# Work_In_Progress.net
KiCad netlist of a schematic drawn in EAGLE
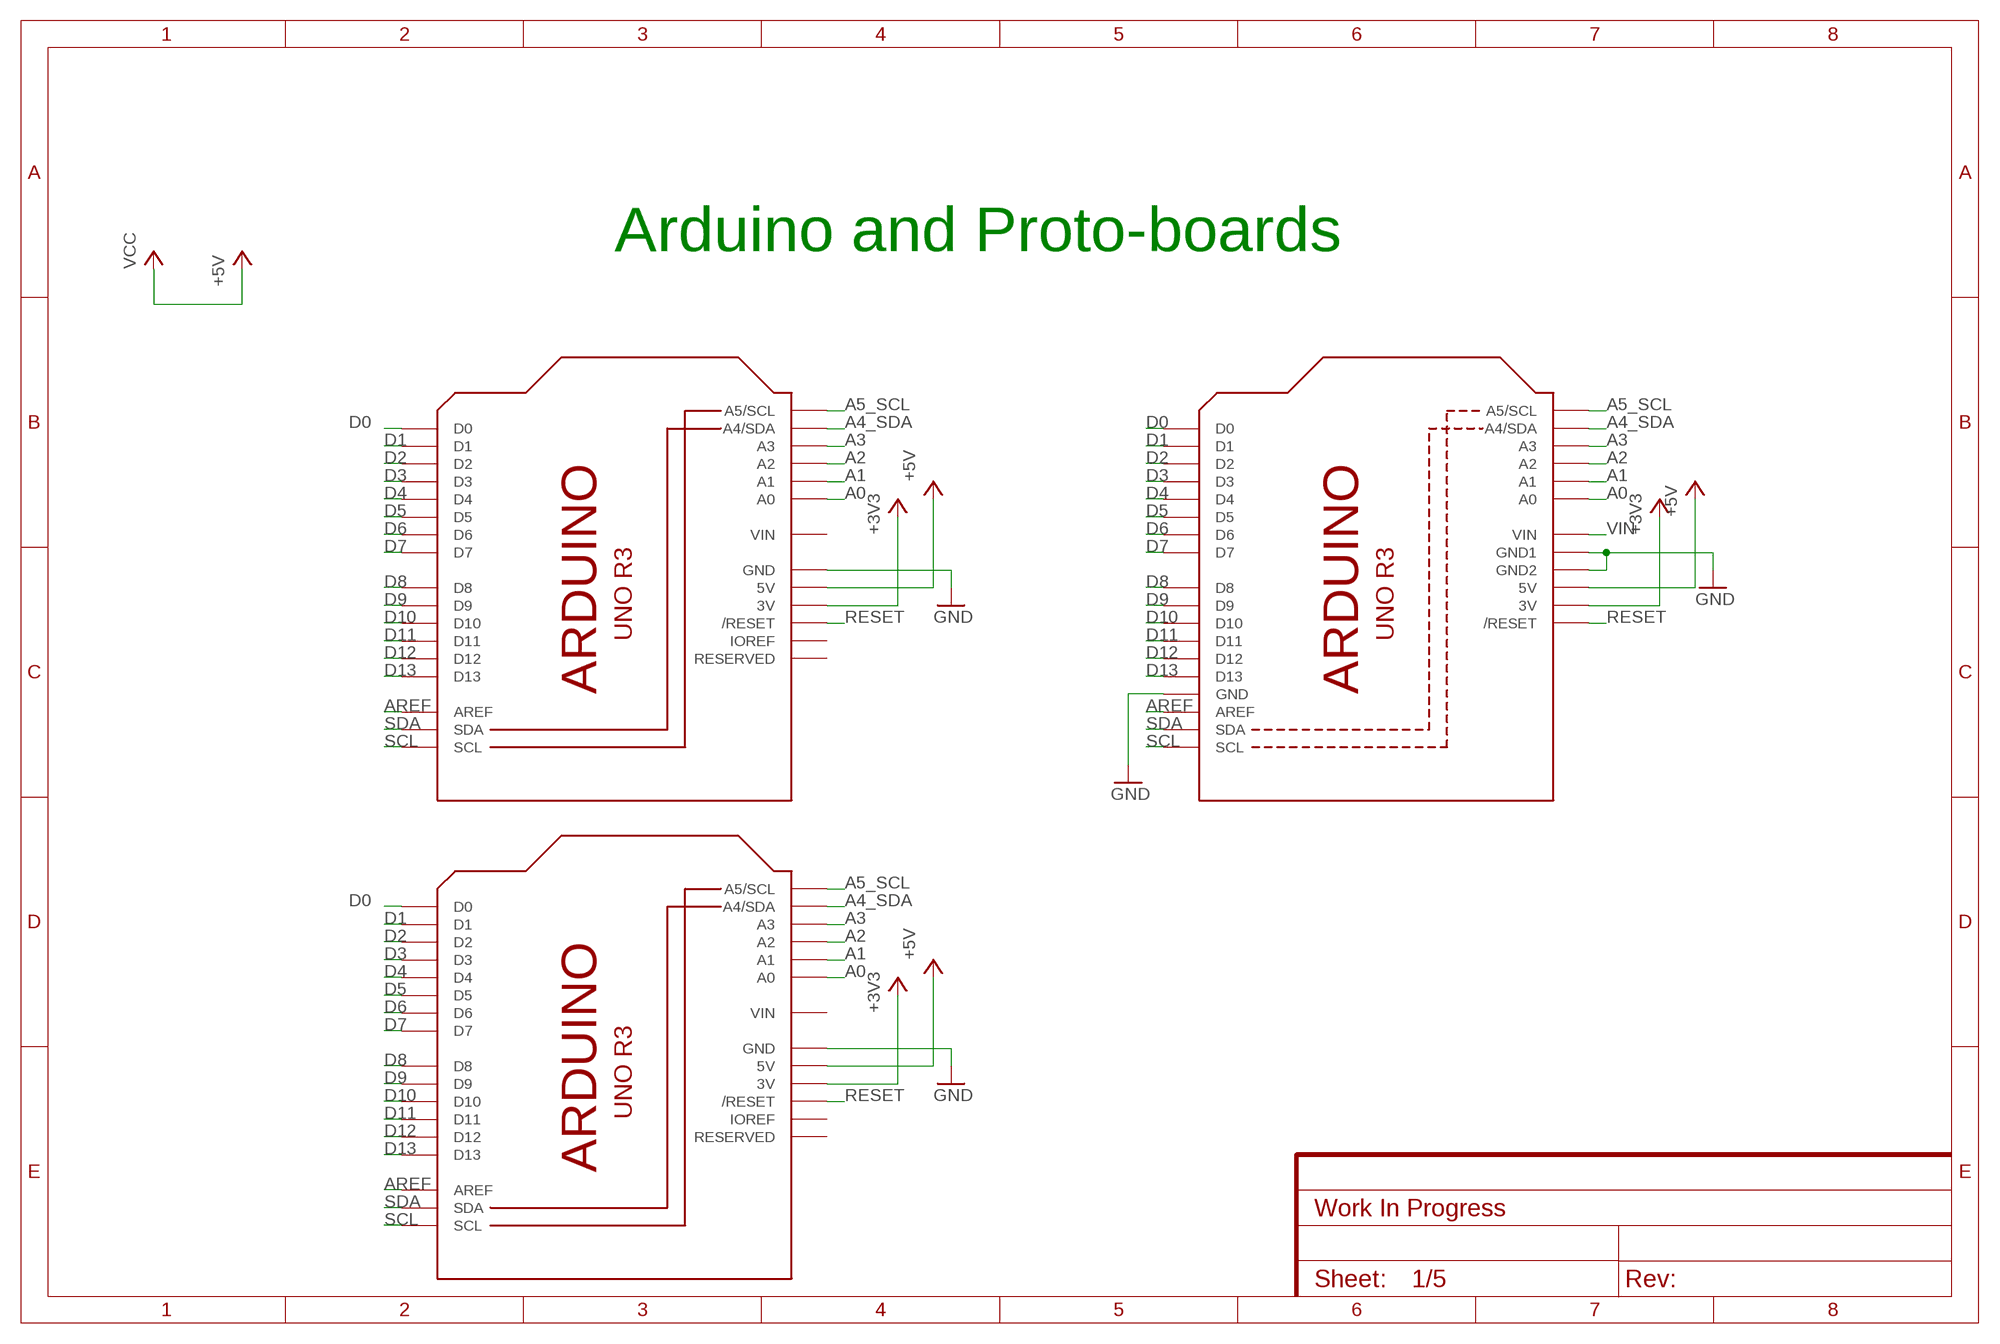
[diagram p0: schematic, sheet 1]
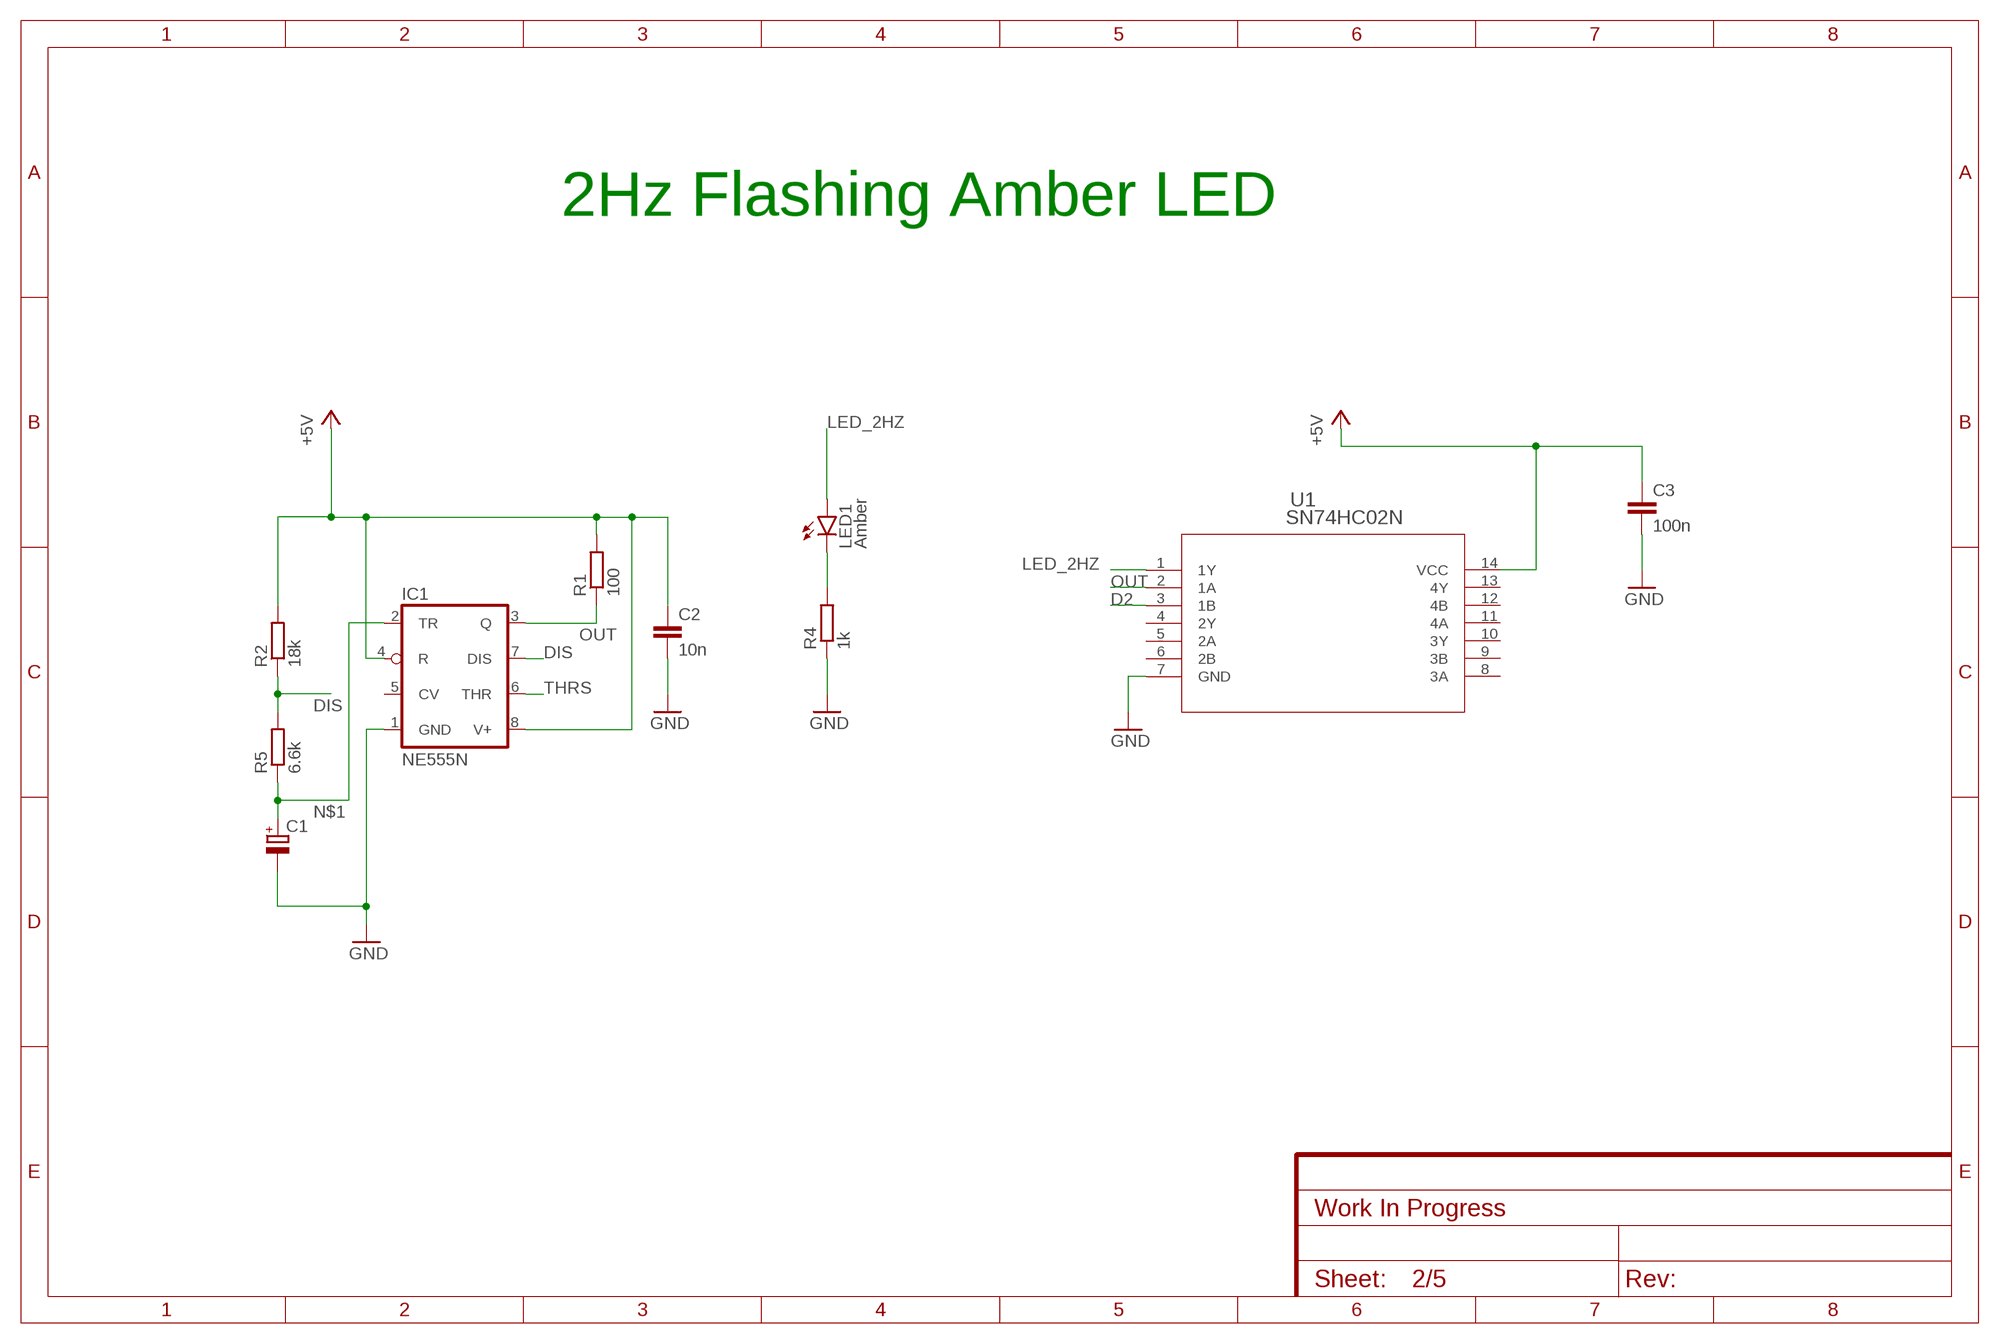
[diagram p1: schematic, sheet 2]
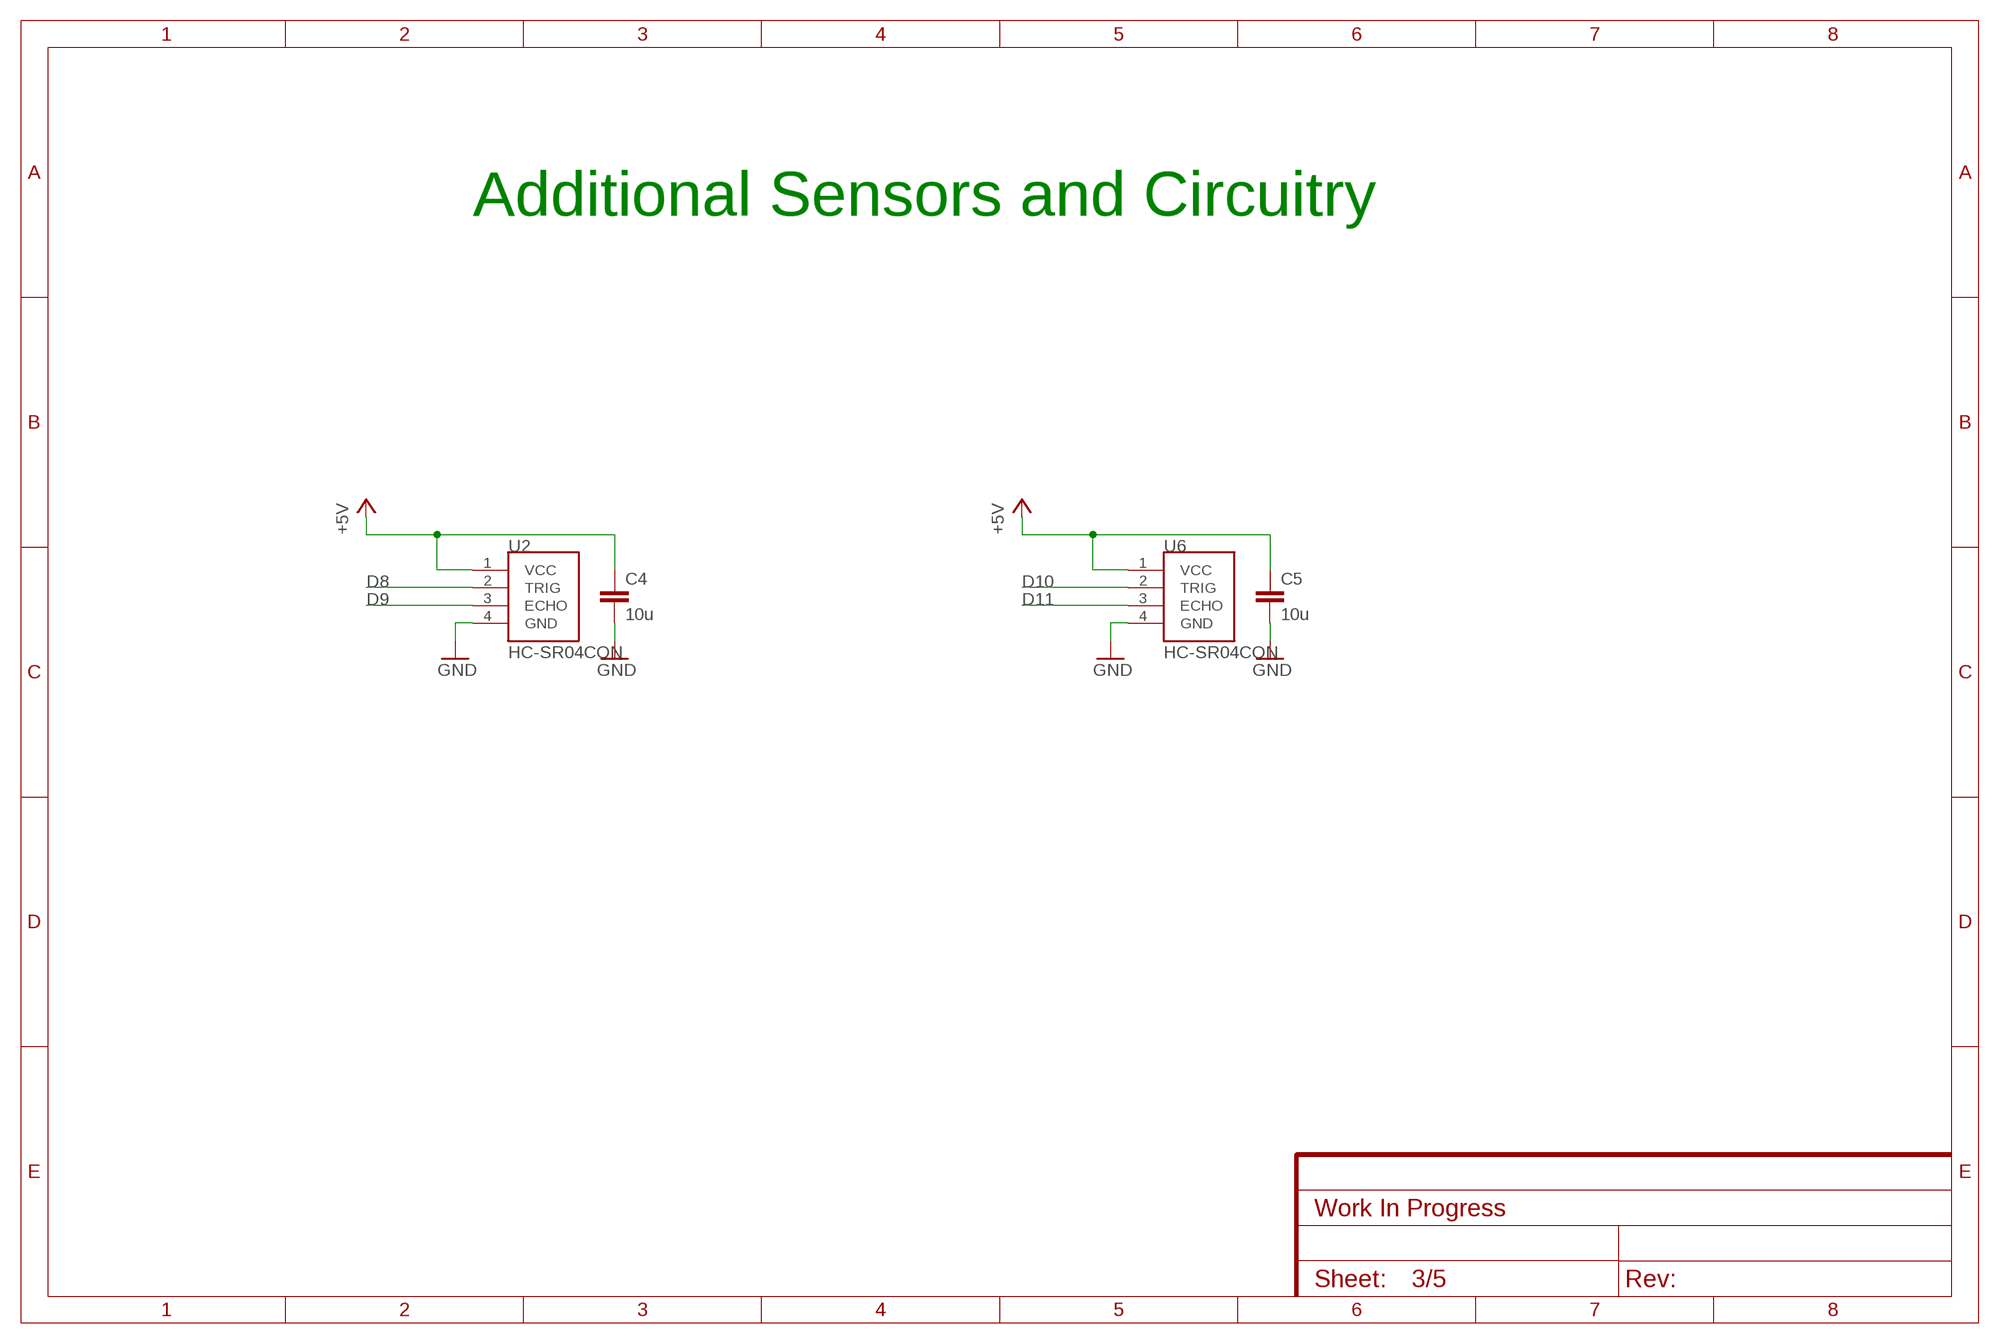
[diagram p2: schematic, sheet 3]
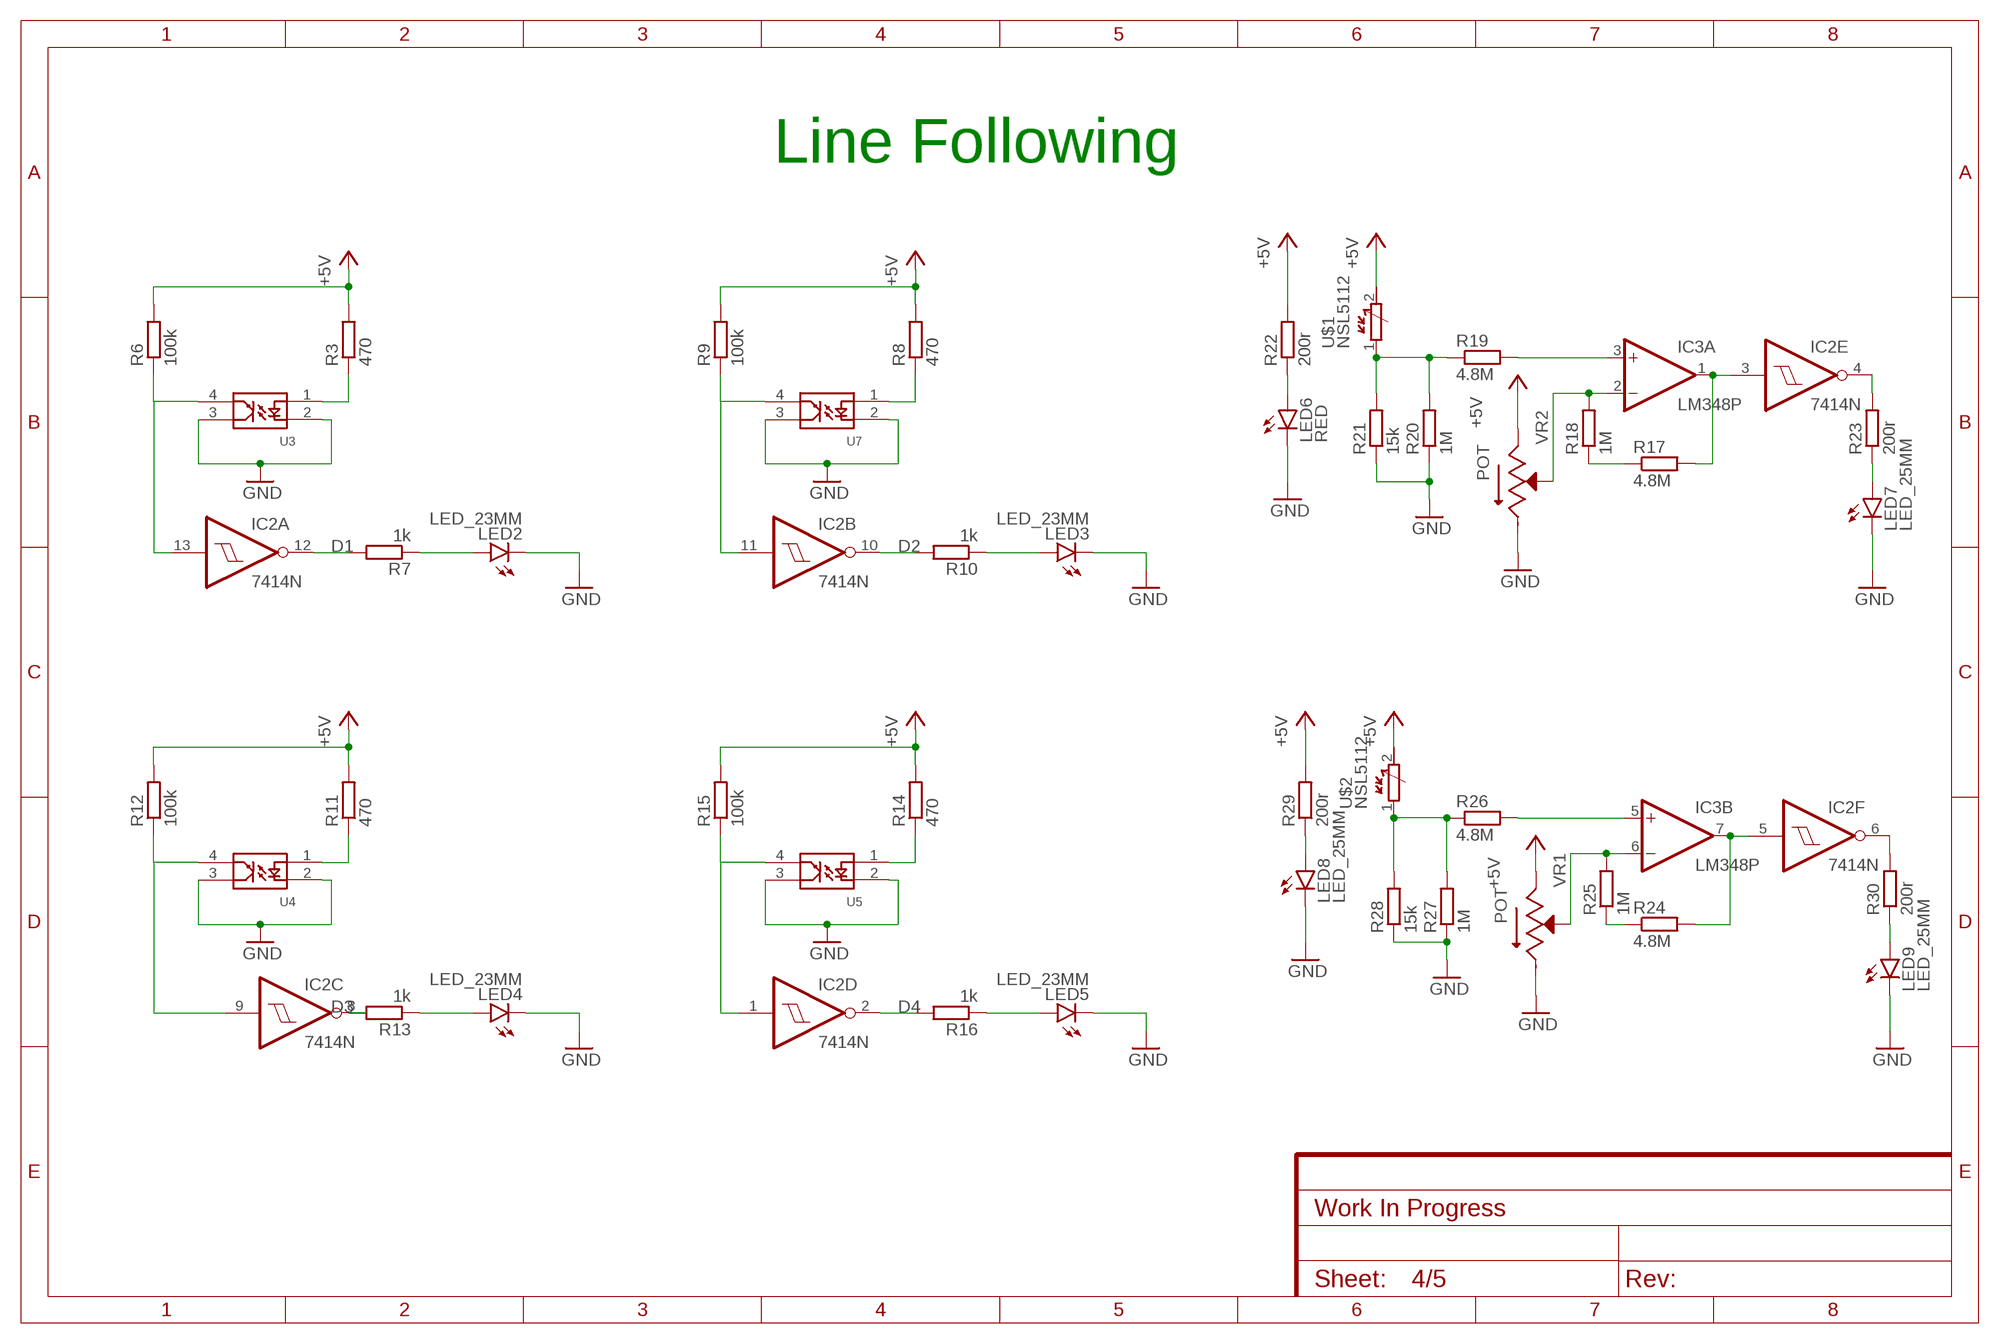
[diagram p3: schematic, sheet 4]
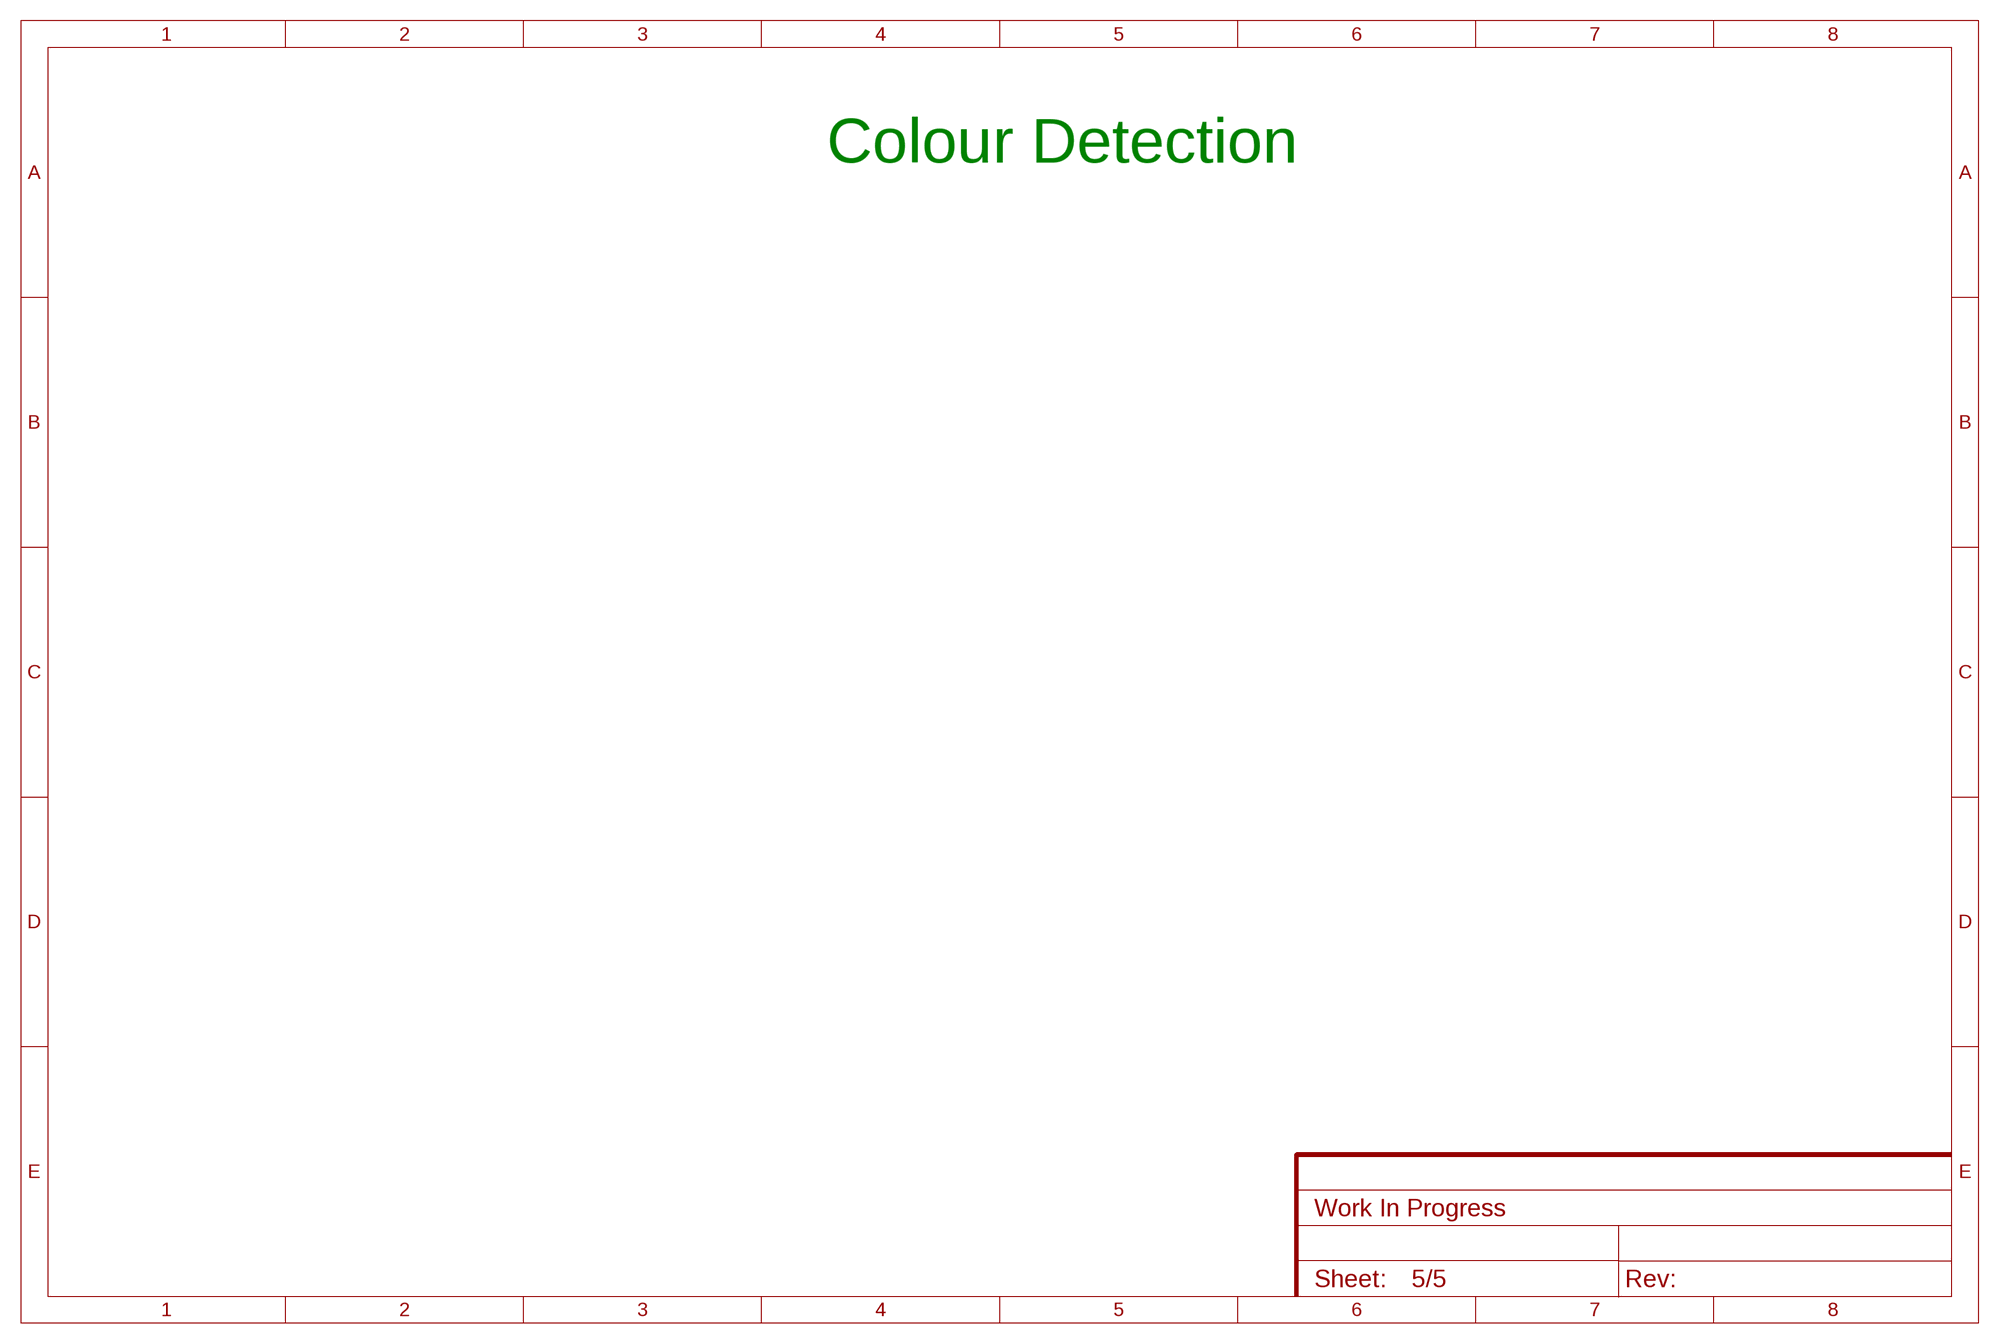
[diagram p4: schematic, sheet 5]

(export (version "E")
  (design (tool "Eeschema 10.0.6"))
  (components
    (comp (ref "M1")
      (value "IDP_PROTOBOARD_LARGE_LARGE")
      (footprint "eagle-import:IDP_PROTO_LARGE")
      (libsource (lib "eagle-import") (part "IDP_PROTOBOARD_LARGE_LARGE"))
    )
    (comp (ref "M2")
      (value "IDP_PROTOBOARD_LARGE_LARGE")
      (footprint "eagle-import:IDP_PROTO_LARGE")
      (libsource (lib "eagle-import") (part "IDP_PROTOBOARD_LARGE_LARGE"))
    )
    (comp (ref "Q1")
      (value "ARDUINOR3-NOIOREF-NOTEXT")
      (footprint "eagle-import:ARDUINOR3-NOTEXT-NOIOREF")
      (libsource (lib "eagle-import") (part "ARDUINOR3-NOIOREF-NOTEXT"))
    )
    (comp (ref "C1")
      (value "CPOL-EUTT2D4")
      (footprint "eagle-import:TT2D4")
      (libsource (lib "eagle-import") (part "CPOL-EUTT2D4"))
    )
    (comp (ref "C2")
      (value "10n")
      (footprint "eagle-import:C025-024X044")
      (libsource (lib "eagle-import") (part "IDP_library_38939663_C-EU025-024X044"))
    )
    (comp (ref "C3")
      (value "100n")
      (footprint "eagle-import:C025-024X044")
      (libsource (lib "eagle-import") (part "IDP_library_38939663_C-EU025-024X044"))
    )
    (comp (ref "IC1")
      (value "NE555N")
      (footprint "eagle-import:DIL08-ROUND")
      (libsource (lib "eagle-import") (part "555NNE"))
    )
    (comp (ref "LED1")
      (value "Amber")
      (footprint "eagle-import:LED3MM")
      (libsource (lib "eagle-import") (part "IDP_library_38939663_LED_23MM"))
    )
    (comp (ref "R1")
      (value "100")
      (footprint "eagle-import:0204V")
      (libsource (lib "eagle-import") (part "IDP_library_38939663_R-EU_0204/2V"))
    )
    (comp (ref "R2")
      (value "18k")
      (footprint "eagle-import:0204V")
      (libsource (lib "eagle-import") (part "IDP_library_38939663_R-EU_0204/2V"))
    )
    (comp (ref "R4")
      (value "1k")
      (footprint "eagle-import:0204V")
      (libsource (lib "eagle-import") (part "IDP_library_38939663_R-EU_0204/2V"))
    )
    (comp (ref "R5")
      (value "6.6k")
      (footprint "eagle-import:0204V")
      (libsource (lib "eagle-import") (part "IDP_library_38939663_R-EU_0204/2V"))
    )
    (comp (ref "U1")
      (value "SN74HC02N")
      (footprint "eagle-import:N14")
      (fields (field (name "COPYRIGHT") "Copyright (C) 2023 Ultra Librarian. All rights reserved."))
      (libsource (lib "eagle-import") (part "SN74HC02N"))
    )
    (comp (ref "C4")
      (value "10u")
      (footprint "eagle-import:C025-024X044")
      (libsource (lib "eagle-import") (part "C-EU025-024X044"))
    )
    (comp (ref "C5")
      (value "10u")
      (footprint "eagle-import:C025-024X044")
      (libsource (lib "eagle-import") (part "C-EU025-024X044"))
    )
    (comp (ref "U2")
      (value "HC-SR04CON")
      (footprint "eagle-import:22-23-2041")
      (libsource (lib "eagle-import") (part "HC-SR04CON"))
    )
    (comp (ref "U6")
      (value "HC-SR04CON")
      (footprint "eagle-import:22-23-2041")
      (libsource (lib "eagle-import") (part "HC-SR04CON"))
    )
    (comp (ref "IC2")
      (value "7414N")
      (footprint "eagle-import:DIL14")
      (libsource (lib "eagle-import") (part "7414N"))
    )
    (comp (ref "IC3")
      (value "LM348P")
      (footprint "eagle-import:DIL14")
      (libsource (lib "eagle-import") (part "LM348P"))
    )
    (comp (ref "LED2")
      (value "LED_23MM")
      (footprint "eagle-import:LED3MM")
      (libsource (lib "eagle-import") (part "IDP_library_38939663_LED_23MM"))
    )
    (comp (ref "LED3")
      (value "LED_23MM")
      (footprint "eagle-import:LED3MM")
      (libsource (lib "eagle-import") (part "IDP_library_38939663_LED_23MM"))
    )
    (comp (ref "LED4")
      (value "LED_23MM")
      (footprint "eagle-import:LED3MM")
      (libsource (lib "eagle-import") (part "IDP_library_38939663_LED_23MM"))
    )
    (comp (ref "LED5")
      (value "LED_23MM")
      (footprint "eagle-import:LED3MM")
      (libsource (lib "eagle-import") (part "IDP_library_38939663_LED_23MM"))
    )
    (comp (ref "LED6")
      (value "RED")
      (footprint "eagle-import:LED5MM")
      (libsource (lib "eagle-import") (part "LED_25MM"))
    )
    (comp (ref "LED7")
      (value "LED_25MM")
      (footprint "eagle-import:LED5MM")
      (libsource (lib "eagle-import") (part "LED_25MM"))
    )
    (comp (ref "LED8")
      (value "LED_25MM")
      (footprint "eagle-import:LED5MM")
      (libsource (lib "eagle-import") (part "LED_25MM"))
    )
    (comp (ref "LED9")
      (value "LED_25MM")
      (footprint "eagle-import:LED5MM")
      (libsource (lib "eagle-import") (part "LED_25MM"))
    )
    (comp (ref "R3")
      (value "470")
      (footprint "eagle-import:0204V")
      (libsource (lib "eagle-import") (part "IDP_library_38939663_R-EU_0204/2V"))
    )
    (comp (ref "R6")
      (value "100k")
      (footprint "eagle-import:0204V")
      (libsource (lib "eagle-import") (part "IDP_library_38939663_R-EU_0204/2V"))
    )
    (comp (ref "R7")
      (value "1k")
      (footprint "eagle-import:0204V")
      (libsource (lib "eagle-import") (part "IDP_library_38939663_R-EU_0204/2V"))
    )
    (comp (ref "R8")
      (value "470")
      (footprint "eagle-import:0204V")
      (libsource (lib "eagle-import") (part "IDP_library_38939663_R-EU_0204/2V"))
    )
    (comp (ref "R9")
      (value "100k")
      (footprint "eagle-import:0204V")
      (libsource (lib "eagle-import") (part "IDP_library_38939663_R-EU_0204/2V"))
    )
    (comp (ref "R10")
      (value "1k")
      (footprint "eagle-import:0204V")
      (libsource (lib "eagle-import") (part "IDP_library_38939663_R-EU_0204/2V"))
    )
    (comp (ref "R11")
      (value "470")
      (footprint "eagle-import:0204V")
      (libsource (lib "eagle-import") (part "IDP_library_38939663_R-EU_0204/2V"))
    )
    (comp (ref "R12")
      (value "100k")
      (footprint "eagle-import:0204V")
      (libsource (lib "eagle-import") (part "IDP_library_38939663_R-EU_0204/2V"))
    )
    (comp (ref "R13")
      (value "1k")
      (footprint "eagle-import:0204V")
      (libsource (lib "eagle-import") (part "IDP_library_38939663_R-EU_0204/2V"))
    )
    (comp (ref "R14")
      (value "470")
      (footprint "eagle-import:0204V")
      (libsource (lib "eagle-import") (part "IDP_library_38939663_R-EU_0204/2V"))
    )
    (comp (ref "R15")
      (value "100k")
      (footprint "eagle-import:0204V")
      (libsource (lib "eagle-import") (part "IDP_library_38939663_R-EU_0204/2V"))
    )
    (comp (ref "R16")
      (value "1k")
      (footprint "eagle-import:0204V")
      (libsource (lib "eagle-import") (part "IDP_library_38939663_R-EU_0204/2V"))
    )
    (comp (ref "R17")
      (value "4.8M")
      (footprint "eagle-import:0204V")
      (libsource (lib "eagle-import") (part "R-EU_0204/2V"))
    )
    (comp (ref "R18")
      (value "1M")
      (footprint "eagle-import:0204V")
      (libsource (lib "eagle-import") (part "R-EU_0204/2V"))
    )
    (comp (ref "R19")
      (value "4.8M")
      (footprint "eagle-import:0204V")
      (libsource (lib "eagle-import") (part "R-EU_0204/2V"))
    )
    (comp (ref "R20")
      (value "1M")
      (footprint "eagle-import:0204V")
      (libsource (lib "eagle-import") (part "R-EU_0204/2V"))
    )
    (comp (ref "R21")
      (value "15k")
      (footprint "eagle-import:0204V")
      (libsource (lib "eagle-import") (part "R-EU_0204/2V"))
    )
    (comp (ref "R22")
      (value "200r")
      (footprint "eagle-import:0204V")
      (libsource (lib "eagle-import") (part "R-EU_0204/2V"))
    )
    (comp (ref "R23")
      (value "200r")
      (footprint "eagle-import:0204V")
      (libsource (lib "eagle-import") (part "R-EU_0204/2V"))
    )
    (comp (ref "R24")
      (value "4.8M")
      (footprint "eagle-import:0204V")
      (libsource (lib "eagle-import") (part "R-EU_0204/2V"))
    )
    (comp (ref "R25")
      (value "1M")
      (footprint "eagle-import:0204V")
      (libsource (lib "eagle-import") (part "R-EU_0204/2V"))
    )
    (comp (ref "R26")
      (value "4.8M")
      (footprint "eagle-import:0204V")
      (libsource (lib "eagle-import") (part "R-EU_0204/2V"))
    )
    (comp (ref "R27")
      (value "1M")
      (footprint "eagle-import:0204V")
      (libsource (lib "eagle-import") (part "R-EU_0204/2V"))
    )
    (comp (ref "R28")
      (value "15k")
      (footprint "eagle-import:0204V")
      (libsource (lib "eagle-import") (part "R-EU_0204/2V"))
    )
    (comp (ref "R29")
      (value "200r")
      (footprint "eagle-import:0204V")
      (libsource (lib "eagle-import") (part "R-EU_0204/2V"))
    )
    (comp (ref "R30")
      (value "200r")
      (footprint "eagle-import:0204V")
      (libsource (lib "eagle-import") (part "R-EU_0204/2V"))
    )
    (comp (ref "U$1")
      (value "NSL5112")
      (footprint "eagle-import:KK-156-2")
      (libsource (lib "eagle-import") (part "NSL5112"))
    )
    (comp (ref "U$2")
      (value "NSL5112")
      (footprint "eagle-import:KK-156-2")
      (libsource (lib "eagle-import") (part "NSL5112"))
    )
    (comp (ref "U3")
      (value "OPB704")
      (footprint "eagle-import:22-23-2041")
      (libsource (lib "eagle-import") (part "OPB704"))
    )
    (comp (ref "U4")
      (value "OPB704")
      (footprint "eagle-import:22-23-2041")
      (libsource (lib "eagle-import") (part "OPB704"))
    )
    (comp (ref "U5")
      (value "OPB704")
      (footprint "eagle-import:22-23-2041")
      (libsource (lib "eagle-import") (part "OPB704"))
    )
    (comp (ref "U7")
      (value "OPB704")
      (footprint "eagle-import:22-23-2041")
      (libsource (lib "eagle-import") (part "OPB704"))
    )
    (comp (ref "VR1")
      (value "POT")
      (footprint "eagle-import:TRIM_3296W-1-250")
      (fields (field (name "MF") "Bourns") (field (name "MP") "3296W-1-250"))
      (libsource (lib "eagle-import") (part "POT"))
    )
    (comp (ref "VR2")
      (value "POT")
      (footprint "eagle-import:TRIM_3296W-1-250")
      (fields (field (name "MF") "Bourns") (field (name "MP") "3296W-1-250"))
      (libsource (lib "eagle-import") (part "POT"))
    )
  )
  (nets
    (net (code "1") (name "+3V3") (class "Default")
      (node (ref "M1") (pin "3V") (pinfunction "3V_3V") (pintype "power_in"))
      (node (ref "M2") (pin "3V") (pinfunction "3V_3V") (pintype "power_in"))
      (node (ref "Q1") (pin "3V") (pinfunction "3V_3V") (pintype "power_in"))
    )
    (net (code "2") (name "+5V") (class "Default")
      (node (ref "C2") (pin "1") (pinfunction "1_1") (pintype "passive"))
      (node (ref "C3") (pin "1") (pinfunction "1_1") (pintype "passive"))
      (node (ref "C4") (pin "1") (pinfunction "1_1") (pintype "passive"))
      (node (ref "C5") (pin "1") (pinfunction "1_1") (pintype "passive"))
      (node (ref "IC1") (pin "4") (pinfunction "R_4") (pintype "input"))
      (node (ref "IC1") (pin "8") (pinfunction "V+_8") (pintype "power_in"))
      (node (ref "M1") (pin "5V") (pinfunction "5V_5V") (pintype "power_in"))
      (node (ref "M1") (pin "5V@0") (pinfunction "5V_5V@0") (pintype "power_in"))
      (node (ref "M1") (pin "5V@1") (pinfunction "5V_5V@1") (pintype "power_in"))
      (node (ref "M1") (pin "5V@10") (pinfunction "5V_5V@10") (pintype "power_in"))
      (node (ref "M1") (pin "5V@11") (pinfunction "5V_5V@11") (pintype "power_in"))
      (node (ref "M1") (pin "5V@12") (pinfunction "5V_5V@12") (pintype "power_in"))
      (node (ref "M1") (pin "5V@13") (pinfunction "5V_5V@13") (pintype "power_in"))
      (node (ref "M1") (pin "5V@14") (pinfunction "5V_5V@14") (pintype "power_in"))
      (node (ref "M1") (pin "5V@15") (pinfunction "5V_5V@15") (pintype "power_in"))
      (node (ref "M1") (pin "5V@16") (pinfunction "5V_5V@16") (pintype "power_in"))
      (node (ref "M1") (pin "5V@17") (pinfunction "5V_5V@17") (pintype "power_in"))
      (node (ref "M1") (pin "5V@18") (pinfunction "5V_5V@18") (pintype "power_in"))
      (node (ref "M1") (pin "5V@19") (pinfunction "5V_5V@19") (pintype "power_in"))
      (node (ref "M1") (pin "5V@2") (pinfunction "5V_5V@2") (pintype "power_in"))
      (node (ref "M1") (pin "5V@20") (pinfunction "5V_5V@20") (pintype "power_in"))
      (node (ref "M1") (pin "5V@21") (pinfunction "5V_5V@21") (pintype "power_in"))
      (node (ref "M1") (pin "5V@22") (pinfunction "5V_5V@22") (pintype "power_in"))
      (node (ref "M1") (pin "5V@23") (pinfunction "5V_5V@23") (pintype "power_in"))
      (node (ref "M1") (pin "5V@24") (pinfunction "5V_5V@24") (pintype "power_in"))
      (node (ref "M1") (pin "5V@25") (pinfunction "5V_5V@25") (pintype "power_in"))
      (node (ref "M1") (pin "5V@26") (pinfunction "5V_5V@26") (pintype "power_in"))
      (node (ref "M1") (pin "5V@27") (pinfunction "5V_5V@27") (pintype "power_in"))
      (node (ref "M1") (pin "5V@28") (pinfunction "5V_5V@28") (pintype "power_in"))
      (node (ref "M1") (pin "5V@29") (pinfunction "5V_5V@29") (pintype "power_in"))
      (node (ref "M1") (pin "5V@3") (pinfunction "5V_5V@3") (pintype "power_in"))
      (node (ref "M1") (pin "5V@30") (pinfunction "5V_5V@30") (pintype "power_in"))
      (node (ref "M1") (pin "5V@31") (pinfunction "5V_5V@31") (pintype "power_in"))
      (node (ref "M1") (pin "5V@32") (pinfunction "5V_5V@32") (pintype "power_in"))
      (node (ref "M1") (pin "5V@33") (pinfunction "5V_5V@33") (pintype "power_in"))
      (node (ref "M1") (pin "5V@34") (pinfunction "5V_5V@34") (pintype "power_in"))
      (node (ref "M1") (pin "5V@35") (pinfunction "5V_5V@35") (pintype "power_in"))
      (node (ref "M1") (pin "5V@36") (pinfunction "5V_5V@36") (pintype "power_in"))
      (node (ref "M1") (pin "5V@37") (pinfunction "5V_5V@37") (pintype "power_in"))
      (node (ref "M1") (pin "5V@38") (pinfunction "5V_5V@38") (pintype "power_in"))
      (node (ref "M1") (pin "5V@39") (pinfunction "5V_5V@39") (pintype "power_in"))
      (node (ref "M1") (pin "5V@4") (pinfunction "5V_5V@4") (pintype "power_in"))
      (node (ref "M1") (pin "5V@40") (pinfunction "5V_5V@40") (pintype "power_in"))
      (node (ref "M1") (pin "5V@41") (pinfunction "5V_5V@41") (pintype "power_in"))
      (node (ref "M1") (pin "5V@42") (pinfunction "5V_5V@42") (pintype "power_in"))
      (node (ref "M1") (pin "5V@43") (pinfunction "5V_5V@43") (pintype "power_in"))
      (node (ref "M1") (pin "5V@44") (pinfunction "5V_5V@44") (pintype "power_in"))
      (node (ref "M1") (pin "5V@45") (pinfunction "5V_5V@45") (pintype "power_in"))
      (node (ref "M1") (pin "5V@46") (pinfunction "5V_5V@46") (pintype "power_in"))
      (node (ref "M1") (pin "5V@47") (pinfunction "5V_5V@47") (pintype "power_in"))
      (node (ref "M1") (pin "5V@48") (pinfunction "5V_5V@48") (pintype "power_in"))
      (node (ref "M1") (pin "5V@49") (pinfunction "5V_5V@49") (pintype "power_in"))
      (node (ref "M1") (pin "5V@5") (pinfunction "5V_5V@5") (pintype "power_in"))
      (node (ref "M1") (pin "5V@50") (pinfunction "5V_5V@50") (pintype "power_in"))
      (node (ref "M1") (pin "5V@51") (pinfunction "5V_5V@51") (pintype "power_in"))
      (node (ref "M1") (pin "5V@52") (pinfunction "5V_5V@52") (pintype "power_in"))
      (node (ref "M1") (pin "5V@53") (pinfunction "5V_5V@53") (pintype "power_in"))
      (node (ref "M1") (pin "5V@54") (pinfunction "5V_5V@54") (pintype "power_in"))
      (node (ref "M1") (pin "5V@55") (pinfunction "5V_5V@55") (pintype "power_in"))
      (node (ref "M1") (pin "5V@56") (pinfunction "5V_5V@56") (pintype "power_in"))
      (node (ref "M1") (pin "5V@57") (pinfunction "5V_5V@57") (pintype "power_in"))
      (node (ref "M1") (pin "5V@58") (pinfunction "5V_5V@58") (pintype "power_in"))
      (node (ref "M1") (pin "5V@59") (pinfunction "5V_5V@59") (pintype "power_in"))
      (node (ref "M1") (pin "5V@6") (pinfunction "5V_5V@6") (pintype "power_in"))
      (node (ref "M1") (pin "5V@60") (pinfunction "5V_5V@60") (pintype "power_in"))
      (node (ref "M1") (pin "5V@61") (pinfunction "5V_5V@61") (pintype "power_in"))
      (node (ref "M1") (pin "5V@62") (pinfunction "5V_5V@62") (pintype "power_in"))
      (node (ref "M1") (pin "5V@63") (pinfunction "5V_5V@63") (pintype "power_in"))
      (node (ref "M1") (pin "5V@64") (pinfunction "5V_5V@64") (pintype "power_in"))
      (node (ref "M1") (pin "5V@65") (pinfunction "5V_5V@65") (pintype "power_in"))
      (node (ref "M1") (pin "5V@66") (pinfunction "5V_5V@66") (pintype "power_in"))
      (node (ref "M1") (pin "5V@67") (pinfunction "5V_5V@67") (pintype "power_in"))
      (node (ref "M1") (pin "5V@68") (pinfunction "5V_5V@68") (pintype "power_in"))
      (node (ref "M1") (pin "5V@69") (pinfunction "5V_5V@69") (pintype "power_in"))
      (node (ref "M1") (pin "5V@7") (pinfunction "5V_5V@7") (pintype "power_in"))
      (node (ref "M1") (pin "5V@70") (pinfunction "5V_5V@70") (pintype "power_in"))
      (node (ref "M1") (pin "5V@8") (pinfunction "5V_5V@8") (pintype "power_in"))
      (node (ref "M1") (pin "5V@9") (pinfunction "5V_5V@9") (pintype "power_in"))
      (node (ref "M2") (pin "5V") (pinfunction "5V_5V") (pintype "power_in"))
      (node (ref "M2") (pin "5V@0") (pinfunction "5V_5V@0") (pintype "power_in"))
      (node (ref "M2") (pin "5V@1") (pinfunction "5V_5V@1") (pintype "power_in"))
      (node (ref "M2") (pin "5V@10") (pinfunction "5V_5V@10") (pintype "power_in"))
      (node (ref "M2") (pin "5V@11") (pinfunction "5V_5V@11") (pintype "power_in"))
      (node (ref "M2") (pin "5V@12") (pinfunction "5V_5V@12") (pintype "power_in"))
      (node (ref "M2") (pin "5V@13") (pinfunction "5V_5V@13") (pintype "power_in"))
      (node (ref "M2") (pin "5V@14") (pinfunction "5V_5V@14") (pintype "power_in"))
      (node (ref "M2") (pin "5V@15") (pinfunction "5V_5V@15") (pintype "power_in"))
      (node (ref "M2") (pin "5V@16") (pinfunction "5V_5V@16") (pintype "power_in"))
      (node (ref "M2") (pin "5V@17") (pinfunction "5V_5V@17") (pintype "power_in"))
      (node (ref "M2") (pin "5V@18") (pinfunction "5V_5V@18") (pintype "power_in"))
      (node (ref "M2") (pin "5V@19") (pinfunction "5V_5V@19") (pintype "power_in"))
      (node (ref "M2") (pin "5V@2") (pinfunction "5V_5V@2") (pintype "power_in"))
      (node (ref "M2") (pin "5V@20") (pinfunction "5V_5V@20") (pintype "power_in"))
      (node (ref "M2") (pin "5V@21") (pinfunction "5V_5V@21") (pintype "power_in"))
      (node (ref "M2") (pin "5V@22") (pinfunction "5V_5V@22") (pintype "power_in"))
      (node (ref "M2") (pin "5V@23") (pinfunction "5V_5V@23") (pintype "power_in"))
      (node (ref "M2") (pin "5V@24") (pinfunction "5V_5V@24") (pintype "power_in"))
      (node (ref "M2") (pin "5V@25") (pinfunction "5V_5V@25") (pintype "power_in"))
      (node (ref "M2") (pin "5V@26") (pinfunction "5V_5V@26") (pintype "power_in"))
      (node (ref "M2") (pin "5V@27") (pinfunction "5V_5V@27") (pintype "power_in"))
      (node (ref "M2") (pin "5V@28") (pinfunction "5V_5V@28") (pintype "power_in"))
      (node (ref "M2") (pin "5V@29") (pinfunction "5V_5V@29") (pintype "power_in"))
      (node (ref "M2") (pin "5V@3") (pinfunction "5V_5V@3") (pintype "power_in"))
      (node (ref "M2") (pin "5V@30") (pinfunction "5V_5V@30") (pintype "power_in"))
      (node (ref "M2") (pin "5V@31") (pinfunction "5V_5V@31") (pintype "power_in"))
      (node (ref "M2") (pin "5V@32") (pinfunction "5V_5V@32") (pintype "power_in"))
      (node (ref "M2") (pin "5V@33") (pinfunction "5V_5V@33") (pintype "power_in"))
      (node (ref "M2") (pin "5V@34") (pinfunction "5V_5V@34") (pintype "power_in"))
      (node (ref "M2") (pin "5V@35") (pinfunction "5V_5V@35") (pintype "power_in"))
      (node (ref "M2") (pin "5V@36") (pinfunction "5V_5V@36") (pintype "power_in"))
      (node (ref "M2") (pin "5V@37") (pinfunction "5V_5V@37") (pintype "power_in"))
      (node (ref "M2") (pin "5V@38") (pinfunction "5V_5V@38") (pintype "power_in"))
      (node (ref "M2") (pin "5V@39") (pinfunction "5V_5V@39") (pintype "power_in"))
      (node (ref "M2") (pin "5V@4") (pinfunction "5V_5V@4") (pintype "power_in"))
      (node (ref "M2") (pin "5V@40") (pinfunction "5V_5V@40") (pintype "power_in"))
      (node (ref "M2") (pin "5V@41") (pinfunction "5V_5V@41") (pintype "power_in"))
      (node (ref "M2") (pin "5V@42") (pinfunction "5V_5V@42") (pintype "power_in"))
      (node (ref "M2") (pin "5V@43") (pinfunction "5V_5V@43") (pintype "power_in"))
      (node (ref "M2") (pin "5V@44") (pinfunction "5V_5V@44") (pintype "power_in"))
      (node (ref "M2") (pin "5V@45") (pinfunction "5V_5V@45") (pintype "power_in"))
      (node (ref "M2") (pin "5V@46") (pinfunction "5V_5V@46") (pintype "power_in"))
      (node (ref "M2") (pin "5V@47") (pinfunction "5V_5V@47") (pintype "power_in"))
      (node (ref "M2") (pin "5V@48") (pinfunction "5V_5V@48") (pintype "power_in"))
      (node (ref "M2") (pin "5V@49") (pinfunction "5V_5V@49") (pintype "power_in"))
      (node (ref "M2") (pin "5V@5") (pinfunction "5V_5V@5") (pintype "power_in"))
      (node (ref "M2") (pin "5V@50") (pinfunction "5V_5V@50") (pintype "power_in"))
      (node (ref "M2") (pin "5V@51") (pinfunction "5V_5V@51") (pintype "power_in"))
      (node (ref "M2") (pin "5V@52") (pinfunction "5V_5V@52") (pintype "power_in"))
      (node (ref "M2") (pin "5V@53") (pinfunction "5V_5V@53") (pintype "power_in"))
      (node (ref "M2") (pin "5V@54") (pinfunction "5V_5V@54") (pintype "power_in"))
      (node (ref "M2") (pin "5V@55") (pinfunction "5V_5V@55") (pintype "power_in"))
      (node (ref "M2") (pin "5V@56") (pinfunction "5V_5V@56") (pintype "power_in"))
      (node (ref "M2") (pin "5V@57") (pinfunction "5V_5V@57") (pintype "power_in"))
      (node (ref "M2") (pin "5V@58") (pinfunction "5V_5V@58") (pintype "power_in"))
      (node (ref "M2") (pin "5V@59") (pinfunction "5V_5V@59") (pintype "power_in"))
      (node (ref "M2") (pin "5V@6") (pinfunction "5V_5V@6") (pintype "power_in"))
      (node (ref "M2") (pin "5V@60") (pinfunction "5V_5V@60") (pintype "power_in"))
      (node (ref "M2") (pin "5V@61") (pinfunction "5V_5V@61") (pintype "power_in"))
      (node (ref "M2") (pin "5V@62") (pinfunction "5V_5V@62") (pintype "power_in"))
      (node (ref "M2") (pin "5V@63") (pinfunction "5V_5V@63") (pintype "power_in"))
      (node (ref "M2") (pin "5V@64") (pinfunction "5V_5V@64") (pintype "power_in"))
      (node (ref "M2") (pin "5V@65") (pinfunction "5V_5V@65") (pintype "power_in"))
      (node (ref "M2") (pin "5V@66") (pinfunction "5V_5V@66") (pintype "power_in"))
      (node (ref "M2") (pin "5V@67") (pinfunction "5V_5V@67") (pintype "power_in"))
      (node (ref "M2") (pin "5V@68") (pinfunction "5V_5V@68") (pintype "power_in"))
      (node (ref "M2") (pin "5V@69") (pinfunction "5V_5V@69") (pintype "power_in"))
      (node (ref "M2") (pin "5V@7") (pinfunction "5V_5V@7") (pintype "power_in"))
      (node (ref "M2") (pin "5V@70") (pinfunction "5V_5V@70") (pintype "power_in"))
      (node (ref "M2") (pin "5V@8") (pinfunction "5V_5V@8") (pintype "power_in"))
      (node (ref "M2") (pin "5V@9") (pinfunction "5V_5V@9") (pintype "power_in"))
      (node (ref "Q1") (pin "5V") (pinfunction "5V_5V") (pintype "power_in"))
      (node (ref "R1") (pin "2") (pinfunction "2_2") (pintype "passive"))
      (node (ref "R11") (pin "2") (pinfunction "2_2") (pintype "passive"))
      (node (ref "R12") (pin "2") (pinfunction "2_2") (pintype "passive"))
      (node (ref "R14") (pin "2") (pinfunction "2_2") (pintype "passive"))
      (node (ref "R15") (pin "2") (pinfunction "2_2") (pintype "passive"))
      (node (ref "R2") (pin "2") (pinfunction "2_2") (pintype "passive"))
      (node (ref "R22") (pin "2") (pinfunction "2_2") (pintype "passive"))
      (node (ref "R29") (pin "2") (pinfunction "2_2") (pintype "passive"))
      (node (ref "R3") (pin "2") (pinfunction "2_2") (pintype "passive"))
      (node (ref "R6") (pin "2") (pinfunction "2_2") (pintype "passive"))
      (node (ref "R8") (pin "2") (pinfunction "2_2") (pintype "passive"))
      (node (ref "R9") (pin "2") (pinfunction "2_2") (pintype "passive"))
      (node (ref "U$1") (pin "2") (pinfunction "E_2") (pintype "passive"))
      (node (ref "U$2") (pin "2") (pinfunction "E_2") (pintype "passive"))
      (node (ref "U1") (pin "14") (pinfunction "VCC_14") (pintype "power_in"))
      (node (ref "U2") (pin "1") (pinfunction "VCC_1") (pintype "power_in"))
      (node (ref "U6") (pin "1") (pinfunction "VCC_1") (pintype "power_in"))
      (node (ref "VR1") (pin "1") (pinfunction "CCW_1") (pintype "passive"))
      (node (ref "VR2") (pin "1") (pinfunction "CCW_1") (pintype "passive"))
    )
    (net (code "3") (name "A0") (class "Default")
      (node (ref "M1") (pin "A0") (pinfunction "A0_A0") (pintype "bidirectional"))
      (node (ref "M2") (pin "A0") (pinfunction "A0_A0") (pintype "bidirectional"))
      (node (ref "Q1") (pin "A0") (pinfunction "A0_A0") (pintype "bidirectional"))
    )
    (net (code "4") (name "A1") (class "Default")
      (node (ref "M1") (pin "A1") (pinfunction "A1_A1") (pintype "bidirectional"))
      (node (ref "M2") (pin "A1") (pinfunction "A1_A1") (pintype "bidirectional"))
      (node (ref "Q1") (pin "A1") (pinfunction "A1_A1") (pintype "bidirectional"))
    )
    (net (code "5") (name "A2") (class "Default")
      (node (ref "M1") (pin "A2") (pinfunction "A2_A2") (pintype "bidirectional"))
      (node (ref "M2") (pin "A2") (pinfunction "A2_A2") (pintype "bidirectional"))
      (node (ref "Q1") (pin "A2") (pinfunction "A2_A2") (pintype "bidirectional"))
    )
    (net (code "6") (name "A3") (class "Default")
      (node (ref "M1") (pin "A3") (pinfunction "A3_A3") (pintype "bidirectional"))
      (node (ref "M2") (pin "A3") (pinfunction "A3_A3") (pintype "bidirectional"))
      (node (ref "Q1") (pin "A3") (pinfunction "A3_A3") (pintype "bidirectional"))
    )
    (net (code "7") (name "A4_SDA") (class "Default")
      (node (ref "M1") (pin "A4") (pinfunction "A4/SDA_A4") (pintype "bidirectional"))
      (node (ref "M2") (pin "A4") (pinfunction "A4/SDA_A4") (pintype "bidirectional"))
      (node (ref "Q1") (pin "A4") (pinfunction "A4/SDA_A4") (pintype "bidirectional"))
    )
    (net (code "8") (name "A5_SCL") (class "Default")
      (node (ref "M1") (pin "A5") (pinfunction "A5/SCL_A5") (pintype "bidirectional"))
      (node (ref "M2") (pin "A5") (pinfunction "A5/SCL_A5") (pintype "bidirectional"))
      (node (ref "Q1") (pin "A5") (pinfunction "A5/SCL_A5") (pintype "bidirectional"))
    )
    (net (code "9") (name "AREF") (class "Default")
      (node (ref "M1") (pin "AREF") (pinfunction "AREF_AREF") (pintype "bidirectional"))
      (node (ref "M2") (pin "AREF") (pinfunction "AREF_AREF") (pintype "bidirectional"))
      (node (ref "Q1") (pin "AREF") (pinfunction "AREF_AREF") (pintype "bidirectional"))
    )
    (net (code "10") (name "D0") (class "Default")
      (node (ref "M1") (pin "D0") (pinfunction "D0_D0") (pintype "bidirectional"))
      (node (ref "M2") (pin "D0") (pinfunction "D0_D0") (pintype "bidirectional"))
      (node (ref "Q1") (pin "D0") (pinfunction "D0_D0") (pintype "bidirectional"))
    )
    (net (code "11") (name "D1") (class "Default")
      (node (ref "IC2") (pin "12") (pinfunction "O_12") (pintype "output"))
      (node (ref "M1") (pin "D1") (pinfunction "D1_D1") (pintype "bidirectional"))
      (node (ref "M2") (pin "D1") (pinfunction "D1_D1") (pintype "bidirectional"))
      (node (ref "Q1") (pin "D1") (pinfunction "D1_D1") (pintype "bidirectional"))
      (node (ref "R7") (pin "2") (pinfunction "2_2") (pintype "passive"))
    )
    (net (code "12") (name "D2") (class "Default")
      (node (ref "IC2") (pin "10") (pinfunction "O_10") (pintype "output"))
      (node (ref "M1") (pin "D2") (pinfunction "D2_D2") (pintype "bidirectional"))
      (node (ref "M2") (pin "D2") (pinfunction "D2_D2") (pintype "bidirectional"))
      (node (ref "Q1") (pin "D2") (pinfunction "D2_D2") (pintype "bidirectional"))
      (node (ref "R10") (pin "2") (pinfunction "2_2") (pintype "passive"))
      (node (ref "U1") (pin "3") (pinfunction "1B_3") (pintype "input"))
    )
    (net (code "13") (name "D3") (class "Default")
      (node (ref "IC2") (pin "8") (pinfunction "O_8") (pintype "output"))
      (node (ref "M1") (pin "D3") (pinfunction "D3_D3") (pintype "bidirectional"))
      (node (ref "M2") (pin "D3") (pinfunction "D3_D3") (pintype "bidirectional"))
      (node (ref "Q1") (pin "D3") (pinfunction "D3_D3") (pintype "bidirectional"))
      (node (ref "R13") (pin "2") (pinfunction "2_2") (pintype "passive"))
    )
    (net (code "14") (name "D4") (class "Default")
      (node (ref "IC2") (pin "2") (pinfunction "O_2") (pintype "output"))
      (node (ref "M1") (pin "D4") (pinfunction "D4_D4") (pintype "bidirectional"))
      (node (ref "M2") (pin "D4") (pinfunction "D4_D4") (pintype "bidirectional"))
      (node (ref "Q1") (pin "D4") (pinfunction "D4_D4") (pintype "bidirectional"))
      (node (ref "R16") (pin "2") (pinfunction "2_2") (pintype "passive"))
    )
    (net (code "15") (name "D5") (class "Default")
      (node (ref "M1") (pin "D5") (pinfunction "D5_D5") (pintype "bidirectional"))
      (node (ref "M2") (pin "D5") (pinfunction "D5_D5") (pintype "bidirectional"))
      (node (ref "Q1") (pin "D5") (pinfunction "D5_D5") (pintype "bidirectional"))
    )
    (net (code "16") (name "D6") (class "Default")
      (node (ref "M1") (pin "D6") (pinfunction "D6_D6") (pintype "bidirectional"))
      (node (ref "M2") (pin "D6") (pinfunction "D6_D6") (pintype "bidirectional"))
      (node (ref "Q1") (pin "D6") (pinfunction "D6_D6") (pintype "bidirectional"))
    )
    (net (code "17") (name "D7") (class "Default")
      (node (ref "M1") (pin "D7") (pinfunction "D7_D7") (pintype "bidirectional"))
      (node (ref "M2") (pin "D7") (pinfunction "D7_D7") (pintype "bidirectional"))
      (node (ref "Q1") (pin "D7") (pinfunction "D7_D7") (pintype "bidirectional"))
    )
    (net (code "18") (name "D8") (class "Default")
      (node (ref "M1") (pin "D8") (pinfunction "D8_D8") (pintype "bidirectional"))
      (node (ref "M2") (pin "D8") (pinfunction "D8_D8") (pintype "bidirectional"))
      (node (ref "Q1") (pin "D8") (pinfunction "D8_D8") (pintype "bidirectional"))
      (node (ref "U2") (pin "2") (pinfunction "TRIG_2") (pintype "bidirectional"))
    )
    (net (code "19") (name "D9") (class "Default")
      (node (ref "M1") (pin "D9") (pinfunction "D9_D9") (pintype "bidirectional"))
      (node (ref "M2") (pin "D9") (pinfunction "D9_D9") (pintype "bidirectional"))
      (node (ref "Q1") (pin "D9") (pinfunction "D9_D9") (pintype "bidirectional"))
      (node (ref "U2") (pin "3") (pinfunction "ECHO_3") (pintype "bidirectional"))
    )
    (net (code "20") (name "D10") (class "Default")
      (node (ref "M1") (pin "D10") (pinfunction "D10_D10") (pintype "bidirectional"))
      (node (ref "M2") (pin "D10") (pinfunction "D10_D10") (pintype "bidirectional"))
      (node (ref "Q1") (pin "D10") (pinfunction "D10_D10") (pintype "bidirectional"))
      (node (ref "U6") (pin "2") (pinfunction "TRIG_2") (pintype "bidirectional"))
    )
    (net (code "21") (name "D11") (class "Default")
      (node (ref "M1") (pin "D11") (pinfunction "D11_D11") (pintype "bidirectional"))
      (node (ref "M2") (pin "D11") (pinfunction "D11_D11") (pintype "bidirectional"))
      (node (ref "Q1") (pin "D11") (pinfunction "D11_D11") (pintype "bidirectional"))
      (node (ref "U6") (pin "3") (pinfunction "ECHO_3") (pintype "bidirectional"))
    )
    (net (code "22") (name "D12") (class "Default")
      (node (ref "M1") (pin "D12") (pinfunction "D12_D12") (pintype "bidirectional"))
      (node (ref "M2") (pin "D12") (pinfunction "D12_D12") (pintype "bidirectional"))
      (node (ref "Q1") (pin "D12") (pinfunction "D12_D12") (pintype "bidirectional"))
    )
    (net (code "23") (name "D13") (class "Default")
      (node (ref "M1") (pin "D13") (pinfunction "D13_D13") (pintype "bidirectional"))
      (node (ref "M2") (pin "D13") (pinfunction "D13_D13") (pintype "bidirectional"))
      (node (ref "Q1") (pin "D13") (pinfunction "D13_D13") (pintype "bidirectional"))
    )
    (net (code "24") (name "DIS") (class "Default")
      (node (ref "IC1") (pin "7") (pinfunction "DIS_7") (pintype "input"))
      (node (ref "R2") (pin "1") (pinfunction "1_1") (pintype "passive"))
      (node (ref "R5") (pin "2") (pinfunction "2_2") (pintype "passive"))
    )
    (net (code "25") (name "GND") (class "Default")
      (node (ref "C1") (pin "-") (pinfunction "-_-") (pintype "passive"))
      (node (ref "C2") (pin "2") (pinfunction "2_2") (pintype "passive"))
      (node (ref "C3") (pin "2") (pinfunction "2_2") (pintype "passive"))
      (node (ref "C4") (pin "2") (pinfunction "2_2") (pintype "passive"))
      (node (ref "C5") (pin "2") (pinfunction "2_2") (pintype "passive"))
      (node (ref "IC1") (pin "1") (pinfunction "GND_1") (pintype "power_in"))
      (node (ref "LED2") (pin "K") (pinfunction "C_K") (pintype "passive"))
      (node (ref "LED3") (pin "K") (pinfunction "C_K") (pintype "passive"))
      (node (ref "LED4") (pin "K") (pinfunction "C_K") (pintype "passive"))
      (node (ref "LED5") (pin "K") (pinfunction "C_K") (pintype "passive"))
      (node (ref "LED6") (pin "K") (pinfunction "C_K") (pintype "passive"))
      (node (ref "LED7") (pin "K") (pinfunction "C_K") (pintype "passive"))
      (node (ref "LED8") (pin "K") (pinfunction "C_K") (pintype "passive"))
      (node (ref "LED9") (pin "K") (pinfunction "C_K") (pintype "passive"))
      (node (ref "M1") (pin "GND") (pinfunction "GND_GND") (pintype "power_in"))
      (node (ref "M1") (pin "GND1") (pinfunction "GND_GND1") (pintype "power_in"))
      (node (ref "M1") (pin "GND10") (pinfunction "GND_GND10") (pintype "power_in"))
      (node (ref "M1") (pin "GND11") (pinfunction "GND_GND11") (pintype "power_in"))
      (node (ref "M1") (pin "GND12") (pinfunction "GND_GND12") (pintype "power_in"))
      (node (ref "M1") (pin "GND13") (pinfunction "GND_GND13") (pintype "power_in"))
      (node (ref "M1") (pin "GND14") (pinfunction "GND_GND14") (pintype "power_in"))
      (node (ref "M1") (pin "GND15") (pinfunction "GND_GND15") (pintype "power_in"))
      (node (ref "M1") (pin "GND16") (pinfunction "GND_GND16") (pintype "power_in"))
      (node (ref "M1") (pin "GND17") (pinfunction "GND_GND17") (pintype "power_in"))
      (node (ref "M1") (pin "GND18") (pinfunction "GND_GND18") (pintype "power_in"))
      (node (ref "M1") (pin "GND19") (pinfunction "GND_GND19") (pintype "power_in"))
      (node (ref "M1") (pin "GND2") (pinfunction "GND_GND2") (pintype "power_in"))
      (node (ref "M1") (pin "GND20") (pinfunction "GND_GND20") (pintype "power_in"))
      (node (ref "M1") (pin "GND21") (pinfunction "GND_GND21") (pintype "power_in"))
      (node (ref "M1") (pin "GND22") (pinfunction "GND_GND22") (pintype "power_in"))
      (node (ref "M1") (pin "GND23") (pinfunction "GND_GND23") (pintype "power_in"))
      (node (ref "M1") (pin "GND24") (pinfunction "GND_GND24") (pintype "power_in"))
      (node (ref "M1") (pin "GND25") (pinfunction "GND_GND25") (pintype "power_in"))
      (node (ref "M1") (pin "GND26") (pinfunction "GND_GND26") (pintype "power_in"))
      (node (ref "M1") (pin "GND27") (pinfunction "GND_GND27") (pintype "power_in"))
      (node (ref "M1") (pin "GND28") (pinfunction "GND_GND28") (pintype "power_in"))
      (node (ref "M1") (pin "GND29") (pinfunction "GND_GND29") (pintype "power_in"))
      (node (ref "M1") (pin "GND3") (pinfunction "GND_GND3") (pintype "power_in"))
      (node (ref "M1") (pin "GND30") (pinfunction "GND_GND30") (pintype "power_in"))
      (node (ref "M1") (pin "GND31") (pinfunction "GND_GND31") (pintype "power_in"))
      (node (ref "M1") (pin "GND32") (pinfunction "GND_GND32") (pintype "power_in"))
      (node (ref "M1") (pin "GND33") (pinfunction "GND_GND33") (pintype "power_in"))
      (node (ref "M1") (pin "GND4") (pinfunction "GND_GND4") (pintype "power_in"))
      (node (ref "M1") (pin "GND5") (pinfunction "GND_GND5") (pintype "power_in"))
      (node (ref "M1") (pin "GND6") (pinfunction "GND_GND6") (pintype "power_in"))
      (node (ref "M1") (pin "GND7") (pinfunction "GND_GND7") (pintype "power_in"))
      (node (ref "M1") (pin "GND8") (pinfunction "GND_GND8") (pintype "power_in"))
      (node (ref "M1") (pin "GND9") (pinfunction "GND_GND9") (pintype "power_in"))
      (node (ref "M1") (pin "GND@1") (pinfunction "GND_GND@1") (pintype "power_in"))
      (node (ref "M1") (pin "GND@10") (pinfunction "GND_GND@10") (pintype "power_in"))
      (node (ref "M1") (pin "GND@11") (pinfunction "GND_GND@11") (pintype "power_in"))
      (node (ref "M1") (pin "GND@12") (pinfunction "GND_GND@12") (pintype "power_in"))
      (node (ref "M1") (pin "GND@13") (pinfunction "GND_GND@13") (pintype "power_in"))
      (node (ref "M1") (pin "GND@14") (pinfunction "GND_GND@14") (pintype "power_in"))
      (node (ref "M1") (pin "GND@15") (pinfunction "GND_GND@15") (pintype "power_in"))
      (node (ref "M1") (pin "GND@16") (pinfunction "GND_GND@16") (pintype "power_in"))
      (node (ref "M1") (pin "GND@17") (pinfunction "GND_GND@17") (pintype "power_in"))
      (node (ref "M1") (pin "GND@2") (pinfunction "GND_GND@2") (pintype "power_in"))
      (node (ref "M1") (pin "GND@26") (pinfunction "GND_GND@26") (pintype "power_in"))
      (node (ref "M1") (pin "GND@27") (pinfunction "GND_GND@27") (pintype "power_in"))
      (node (ref "M1") (pin "GND@28") (pinfunction "GND_GND@28") (pintype "power_in"))
      (node (ref "M1") (pin "GND@29") (pinfunction "GND_GND@29") (pintype "power_in"))
      (node (ref "M1") (pin "GND@3") (pinfunction "GND_GND@3") (pintype "power_in"))
      (node (ref "M1") (pin "GND@30") (pinfunction "GND_GND@30") (pintype "power_in"))
      (node (ref "M1") (pin "GND@31") (pinfunction "GND_GND@31") (pintype "power_in"))
      (node (ref "M1") (pin "GND@32") (pinfunction "GND_GND@32") (pintype "power_in"))
      (node (ref "M1") (pin "GND@33") (pinfunction "GND_GND@33") (pintype "power_in"))
      (node (ref "M1") (pin "GND@34") (pinfunction "GND_GND@34") (pintype "power_in"))
      (node (ref "M1") (pin "GND@35") (pinfunction "GND_GND@35") (pintype "power_in"))
      (node (ref "M1") (pin "GND@36") (pinfunction "GND_GND@36") (pintype "power_in"))
      (node (ref "M1") (pin "GND@37") (pinfunction "GND_GND@37") (pintype "power_in"))
      (node (ref "M1") (pin "GND@38") (pinfunction "GND_GND@38") (pintype "power_in"))
      (node (ref "M1") (pin "GND@39") (pinfunction "GND_GND@39") (pintype "power_in"))
      (node (ref "M1") (pin "GND@4") (pinfunction "GND_GND@4") (pintype "power_in"))
      (node (ref "M1") (pin "GND@40") (pinfunction "GND_GND@40") (pintype "power_in"))
      (node (ref "M1") (pin "GND@41") (pinfunction "GND_GND@41") (pintype "power_in"))
      (node (ref "M1") (pin "GND@42") (pinfunction "GND_GND@42") (pintype "power_in"))
      (node (ref "M1") (pin "GND@43") (pinfunction "GND_GND@43") (pintype "power_in"))
      (node (ref "M1") (pin "GND@44") (pinfunction "GND_GND@44") (pintype "power_in"))
      (node (ref "M1") (pin "GND@45") (pinfunction "GND_GND@45") (pintype "power_in"))
      (node (ref "M1") (pin "GND@46") (pinfunction "GND_GND@46") (pintype "power_in"))
      (node (ref "M1") (pin "GND@47") (pinfunction "GND_GND@47") (pintype "power_in"))
      (node (ref "M1") (pin "GND@48") (pinfunction "GND_GND@48") (pintype "power_in"))
      (node (ref "M1") (pin "GND@5") (pinfunction "GND_GND@5") (pintype "power_in"))
      (node (ref "M1") (pin "GND@6") (pinfunction "GND_GND@6") (pintype "power_in"))
      (node (ref "M1") (pin "GND@7") (pinfunction "GND_GND@7") (pintype "power_in"))
      (node (ref "M1") (pin "GND@8") (pinfunction "GND_GND@8") (pintype "power_in"))
      (node (ref "M1") (pin "GND@9") (pinfunction "GND_GND@9") (pintype "power_in"))
      (node (ref "M2") (pin "GND") (pinfunction "GND_GND") (pintype "power_in"))
      (node (ref "M2") (pin "GND1") (pinfunction "GND_GND1") (pintype "power_in"))
      (node (ref "M2") (pin "GND10") (pinfunction "GND_GND10") (pintype "power_in"))
      (node (ref "M2") (pin "GND11") (pinfunction "GND_GND11") (pintype "power_in"))
      (node (ref "M2") (pin "GND12") (pinfunction "GND_GND12") (pintype "power_in"))
      (node (ref "M2") (pin "GND13") (pinfunction "GND_GND13") (pintype "power_in"))
      (node (ref "M2") (pin "GND14") (pinfunction "GND_GND14") (pintype "power_in"))
      (node (ref "M2") (pin "GND15") (pinfunction "GND_GND15") (pintype "power_in"))
      (node (ref "M2") (pin "GND16") (pinfunction "GND_GND16") (pintype "power_in"))
      (node (ref "M2") (pin "GND17") (pinfunction "GND_GND17") (pintype "power_in"))
      (node (ref "M2") (pin "GND18") (pinfunction "GND_GND18") (pintype "power_in"))
      (node (ref "M2") (pin "GND19") (pinfunction "GND_GND19") (pintype "power_in"))
      (node (ref "M2") (pin "GND2") (pinfunction "GND_GND2") (pintype "power_in"))
      (node (ref "M2") (pin "GND20") (pinfunction "GND_GND20") (pintype "power_in"))
      (node (ref "M2") (pin "GND21") (pinfunction "GND_GND21") (pintype "power_in"))
      (node (ref "M2") (pin "GND22") (pinfunction "GND_GND22") (pintype "power_in"))
      (node (ref "M2") (pin "GND23") (pinfunction "GND_GND23") (pintype "power_in"))
      (node (ref "M2") (pin "GND24") (pinfunction "GND_GND24") (pintype "power_in"))
      (node (ref "M2") (pin "GND25") (pinfunction "GND_GND25") (pintype "power_in"))
      (node (ref "M2") (pin "GND26") (pinfunction "GND_GND26") (pintype "power_in"))
      (node (ref "M2") (pin "GND27") (pinfunction "GND_GND27") (pintype "power_in"))
      (node (ref "M2") (pin "GND28") (pinfunction "GND_GND28") (pintype "power_in"))
      (node (ref "M2") (pin "GND29") (pinfunction "GND_GND29") (pintype "power_in"))
      (node (ref "M2") (pin "GND3") (pinfunction "GND_GND3") (pintype "power_in"))
      (node (ref "M2") (pin "GND30") (pinfunction "GND_GND30") (pintype "power_in"))
      (node (ref "M2") (pin "GND31") (pinfunction "GND_GND31") (pintype "power_in"))
      (node (ref "M2") (pin "GND32") (pinfunction "GND_GND32") (pintype "power_in"))
      (node (ref "M2") (pin "GND33") (pinfunction "GND_GND33") (pintype "power_in"))
      (node (ref "M2") (pin "GND4") (pinfunction "GND_GND4") (pintype "power_in"))
      (node (ref "M2") (pin "GND5") (pinfunction "GND_GND5") (pintype "power_in"))
      (node (ref "M2") (pin "GND6") (pinfunction "GND_GND6") (pintype "power_in"))
      (node (ref "M2") (pin "GND7") (pinfunction "GND_GND7") (pintype "power_in"))
      (node (ref "M2") (pin "GND8") (pinfunction "GND_GND8") (pintype "power_in"))
      (node (ref "M2") (pin "GND9") (pinfunction "GND_GND9") (pintype "power_in"))
      (node (ref "M2") (pin "GND@1") (pinfunction "GND_GND@1") (pintype "power_in"))
      (node (ref "M2") (pin "GND@10") (pinfunction "GND_GND@10") (pintype "power_in"))
      (node (ref "M2") (pin "GND@11") (pinfunction "GND_GND@11") (pintype "power_in"))
      (node (ref "M2") (pin "GND@12") (pinfunction "GND_GND@12") (pintype "power_in"))
      (node (ref "M2") (pin "GND@13") (pinfunction "GND_GND@13") (pintype "power_in"))
      (node (ref "M2") (pin "GND@14") (pinfunction "GND_GND@14") (pintype "power_in"))
      (node (ref "M2") (pin "GND@15") (pinfunction "GND_GND@15") (pintype "power_in"))
      (node (ref "M2") (pin "GND@16") (pinfunction "GND_GND@16") (pintype "power_in"))
      (node (ref "M2") (pin "GND@17") (pinfunction "GND_GND@17") (pintype "power_in"))
      (node (ref "M2") (pin "GND@2") (pinfunction "GND_GND@2") (pintype "power_in"))
      (node (ref "M2") (pin "GND@26") (pinfunction "GND_GND@26") (pintype "power_in"))
      (node (ref "M2") (pin "GND@27") (pinfunction "GND_GND@27") (pintype "power_in"))
      (node (ref "M2") (pin "GND@28") (pinfunction "GND_GND@28") (pintype "power_in"))
      (node (ref "M2") (pin "GND@29") (pinfunction "GND_GND@29") (pintype "power_in"))
      (node (ref "M2") (pin "GND@3") (pinfunction "GND_GND@3") (pintype "power_in"))
      (node (ref "M2") (pin "GND@30") (pinfunction "GND_GND@30") (pintype "power_in"))
      (node (ref "M2") (pin "GND@31") (pinfunction "GND_GND@31") (pintype "power_in"))
      (node (ref "M2") (pin "GND@32") (pinfunction "GND_GND@32") (pintype "power_in"))
      (node (ref "M2") (pin "GND@33") (pinfunction "GND_GND@33") (pintype "power_in"))
      (node (ref "M2") (pin "GND@34") (pinfunction "GND_GND@34") (pintype "power_in"))
      (node (ref "M2") (pin "GND@35") (pinfunction "GND_GND@35") (pintype "power_in"))
      (node (ref "M2") (pin "GND@36") (pinfunction "GND_GND@36") (pintype "power_in"))
      (node (ref "M2") (pin "GND@37") (pinfunction "GND_GND@37") (pintype "power_in"))
      (node (ref "M2") (pin "GND@38") (pinfunction "GND_GND@38") (pintype "power_in"))
      (node (ref "M2") (pin "GND@39") (pinfunction "GND_GND@39") (pintype "power_in"))
      (node (ref "M2") (pin "GND@4") (pinfunction "GND_GND@4") (pintype "power_in"))
      (node (ref "M2") (pin "GND@40") (pinfunction "GND_GND@40") (pintype "power_in"))
      (node (ref "M2") (pin "GND@41") (pinfunction "GND_GND@41") (pintype "power_in"))
      (node (ref "M2") (pin "GND@42") (pinfunction "GND_GND@42") (pintype "power_in"))
      (node (ref "M2") (pin "GND@43") (pinfunction "GND_GND@43") (pintype "power_in"))
      (node (ref "M2") (pin "GND@44") (pinfunction "GND_GND@44") (pintype "power_in"))
      (node (ref "M2") (pin "GND@45") (pinfunction "GND_GND@45") (pintype "power_in"))
      (node (ref "M2") (pin "GND@46") (pinfunction "GND_GND@46") (pintype "power_in"))
      (node (ref "M2") (pin "GND@47") (pinfunction "GND_GND@47") (pintype "power_in"))
      (node (ref "M2") (pin "GND@48") (pinfunction "GND_GND@48") (pintype "power_in"))
      (node (ref "M2") (pin "GND@5") (pinfunction "GND_GND@5") (pintype "power_in"))
      (node (ref "M2") (pin "GND@6") (pinfunction "GND_GND@6") (pintype "power_in"))
      (node (ref "M2") (pin "GND@7") (pinfunction "GND_GND@7") (pintype "power_in"))
      (node (ref "M2") (pin "GND@8") (pinfunction "GND_GND@8") (pintype "power_in"))
      (node (ref "M2") (pin "GND@9") (pinfunction "GND_GND@9") (pintype "power_in"))
      (node (ref "Q1") (pin "GND") (pinfunction "GND_GND") (pintype "power_in"))
      (node (ref "Q1") (pin "GND1") (pinfunction "GND1_GND1") (pintype "power_in"))
      (node (ref "Q1") (pin "GND2") (pinfunction "GND2_GND2") (pintype "power_in"))
      (node (ref "R20") (pin "1") (pinfunction "1_1") (pintype "passive"))
      (node (ref "R21") (pin "1") (pinfunction "1_1") (pintype "passive"))
      (node (ref "R27") (pin "1") (pinfunction "1_1") (pintype "passive"))
      (node (ref "R28") (pin "1") (pinfunction "1_1") (pintype "passive"))
      (node (ref "R4") (pin "1") (pinfunction "1_1") (pintype "passive"))
      (node (ref "U1") (pin "7") (pinfunction "GND_7") (pintype "power_in"))
      (node (ref "U2") (pin "4") (pinfunction "GND_4") (pintype "power_in"))
      (node (ref "U3") (pin "2") (pinfunction "1_2") (pintype "bidirectional"))
      (node (ref "U3") (pin "3") (pinfunction "3_3") (pintype "bidirectional"))
      (node (ref "U4") (pin "2") (pinfunction "1_2") (pintype "bidirectional"))
      (node (ref "U4") (pin "3") (pinfunction "3_3") (pintype "bidirectional"))
      (node (ref "U5") (pin "2") (pinfunction "1_2") (pintype "bidirectional"))
      (node (ref "U5") (pin "3") (pinfunction "3_3") (pintype "bidirectional"))
      (node (ref "U6") (pin "4") (pinfunction "GND_4") (pintype "power_in"))
      (node (ref "U7") (pin "2") (pinfunction "1_2") (pintype "bidirectional"))
      (node (ref "U7") (pin "3") (pinfunction "3_3") (pintype "bidirectional"))
      (node (ref "VR1") (pin "3") (pinfunction "CW_3") (pintype "passive"))
      (node (ref "VR2") (pin "3") (pinfunction "CW_3") (pintype "passive"))
    )
    (net (code "26") (name "LED_2HZ") (class "Default")
      (node (ref "LED1") (pin "A") (pinfunction "A_A") (pintype "passive"))
      (node (ref "U1") (pin "1") (pinfunction "1Y_1") (pintype "output"))
    )
    (net (code "27") (name "N$1") (class "Default")
      (node (ref "C1") (pin "+") (pinfunction "+_+") (pintype "passive"))
      (node (ref "IC1") (pin "2") (pinfunction "TR_2") (pintype "input"))
      (node (ref "R5") (pin "1") (pinfunction "1_1") (pintype "passive"))
    )
    (net (code "28") (name "Net-(IC2A-I)") (class "Default")
      (node (ref "IC2") (pin "13") (pinfunction "I_13") (pintype "input"))
      (node (ref "R6") (pin "1") (pinfunction "1_1") (pintype "passive"))
      (node (ref "U3") (pin "4") (pinfunction "4_4") (pintype "bidirectional"))
    )
    (net (code "29") (name "Net-(IC2B-I)") (class "Default")
      (node (ref "IC2") (pin "11") (pinfunction "I_11") (pintype "input"))
      (node (ref "R9") (pin "1") (pinfunction "1_1") (pintype "passive"))
      (node (ref "U7") (pin "4") (pinfunction "4_4") (pintype "bidirectional"))
    )
    (net (code "30") (name "Net-(IC2C-I)") (class "Default")
      (node (ref "IC2") (pin "9") (pinfunction "I_9") (pintype "input"))
      (node (ref "R12") (pin "1") (pinfunction "1_1") (pintype "passive"))
      (node (ref "U4") (pin "4") (pinfunction "4_4") (pintype "bidirectional"))
    )
    (net (code "31") (name "Net-(IC2D-I)") (class "Default")
      (node (ref "IC2") (pin "1") (pinfunction "I_1") (pintype "input"))
      (node (ref "R15") (pin "1") (pinfunction "1_1") (pintype "passive"))
      (node (ref "U5") (pin "4") (pinfunction "4_4") (pintype "bidirectional"))
    )
    (net (code "32") (name "Net-(IC2E-I)") (class "Default")
      (node (ref "IC2") (pin "3") (pinfunction "I_3") (pintype "input"))
      (node (ref "IC3") (pin "1") (pinfunction "OUT_1") (pintype "output"))
      (node (ref "R17") (pin "2") (pinfunction "2_2") (pintype "passive"))
    )
    (net (code "33") (name "Net-(IC2E-O)") (class "Default")
      (node (ref "IC2") (pin "4") (pinfunction "O_4") (pintype "output"))
      (node (ref "R23") (pin "2") (pinfunction "2_2") (pintype "passive"))
    )
    (net (code "34") (name "Net-(IC2F-I)") (class "Default")
      (node (ref "IC2") (pin "5") (pinfunction "I_5") (pintype "input"))
      (node (ref "IC3") (pin "7") (pinfunction "OUT_7") (pintype "output"))
      (node (ref "R24") (pin "2") (pinfunction "2_2") (pintype "passive"))
    )
    (net (code "35") (name "Net-(IC2F-O)") (class "Default")
      (node (ref "IC2") (pin "6") (pinfunction "O_6") (pintype "output"))
      (node (ref "R30") (pin "2") (pinfunction "2_2") (pintype "passive"))
    )
    (net (code "36") (name "Net-(IC3A-+IN)") (class "Default")
      (node (ref "IC3") (pin "3") (pinfunction "+IN_3") (pintype "input"))
      (node (ref "R19") (pin "2") (pinfunction "2_2") (pintype "passive"))
    )
    (net (code "37") (name "Net-(IC3A--IN)") (class "Default")
      (node (ref "IC3") (pin "2") (pinfunction "-IN_2") (pintype "input"))
      (node (ref "R18") (pin "2") (pinfunction "2_2") (pintype "passive"))
      (node (ref "VR2") (pin "2") (pinfunction "WIPER_2") (pintype "passive"))
    )
    (net (code "38") (name "Net-(IC3B-+IN)") (class "Default")
      (node (ref "IC3") (pin "5") (pinfunction "+IN_5") (pintype "input"))
      (node (ref "R26") (pin "2") (pinfunction "2_2") (pintype "passive"))
    )
    (net (code "39") (name "Net-(IC3B--IN)") (class "Default")
      (node (ref "IC3") (pin "6") (pinfunction "-IN_6") (pintype "input"))
      (node (ref "R25") (pin "2") (pinfunction "2_2") (pintype "passive"))
      (node (ref "VR1") (pin "2") (pinfunction "WIPER_2") (pintype "passive"))
    )
    (net (code "40") (name "Net-(LED1-C)") (class "Default")
      (node (ref "LED1") (pin "K") (pinfunction "C_K") (pintype "passive"))
      (node (ref "R4") (pin "2") (pinfunction "2_2") (pintype "passive"))
    )
    (net (code "41") (name "Net-(LED2-PadA)") (class "Default")
      (node (ref "LED2") (pin "A") (pinfunction "A_A") (pintype "passive"))
      (node (ref "R7") (pin "1") (pinfunction "1_1") (pintype "passive"))
    )
    (net (code "42") (name "Net-(LED3-PadA)") (class "Default")
      (node (ref "LED3") (pin "A") (pinfunction "A_A") (pintype "passive"))
      (node (ref "R10") (pin "1") (pinfunction "1_1") (pintype "passive"))
    )
    (net (code "43") (name "Net-(LED4-PadA)") (class "Default")
      (node (ref "LED4") (pin "A") (pinfunction "A_A") (pintype "passive"))
      (node (ref "R13") (pin "1") (pinfunction "1_1") (pintype "passive"))
    )
    (net (code "44") (name "Net-(LED5-PadA)") (class "Default")
      (node (ref "LED5") (pin "A") (pinfunction "A_A") (pintype "passive"))
      (node (ref "R16") (pin "1") (pinfunction "1_1") (pintype "passive"))
    )
    (net (code "45") (name "Net-(LED6-PadA)") (class "Default")
      (node (ref "LED6") (pin "A") (pinfunction "A_A") (pintype "passive"))
      (node (ref "R22") (pin "1") (pinfunction "1_1") (pintype "passive"))
    )
    (net (code "46") (name "Net-(LED7-PadA)") (class "Default")
      (node (ref "LED7") (pin "A") (pinfunction "A_A") (pintype "passive"))
      (node (ref "R23") (pin "1") (pinfunction "1_1") (pintype "passive"))
    )
    (net (code "47") (name "Net-(LED8-PadA)") (class "Default")
      (node (ref "LED8") (pin "A") (pinfunction "A_A") (pintype "passive"))
      (node (ref "R29") (pin "1") (pinfunction "1_1") (pintype "passive"))
    )
    (net (code "48") (name "Net-(LED9-PadA)") (class "Default")
      (node (ref "LED9") (pin "A") (pinfunction "A_A") (pintype "passive"))
      (node (ref "R30") (pin "1") (pinfunction "1_1") (pintype "passive"))
    )
    (net (code "49") (name "Net-(R17-Pad1)") (class "Default")
      (node (ref "R17") (pin "1") (pinfunction "1_1") (pintype "passive"))
      (node (ref "R18") (pin "1") (pinfunction "1_1") (pintype "passive"))
    )
    (net (code "50") (name "Net-(R24-Pad1)") (class "Default")
      (node (ref "R24") (pin "1") (pinfunction "1_1") (pintype "passive"))
      (node (ref "R25") (pin "1") (pinfunction "1_1") (pintype "passive"))
    )
    (net (code "51") (name "Net-(U$1-A)") (class "Default")
      (node (ref "R19") (pin "1") (pinfunction "1_1") (pintype "passive"))
      (node (ref "R20") (pin "2") (pinfunction "2_2") (pintype "passive"))
      (node (ref "R21") (pin "2") (pinfunction "2_2") (pintype "passive"))
      (node (ref "U$1") (pin "1") (pinfunction "A_1") (pintype "passive"))
    )
    (net (code "52") (name "Net-(U$2-A)") (class "Default")
      (node (ref "R26") (pin "1") (pinfunction "1_1") (pintype "passive"))
      (node (ref "R27") (pin "2") (pinfunction "2_2") (pintype "passive"))
      (node (ref "R28") (pin "2") (pinfunction "2_2") (pintype "passive"))
      (node (ref "U$2") (pin "1") (pinfunction "A_1") (pintype "passive"))
    )
    (net (code "53") (name "Net-(U3-2)") (class "Default")
      (node (ref "R3") (pin "1") (pinfunction "1_1") (pintype "passive"))
      (node (ref "U3") (pin "1") (pinfunction "2_1") (pintype "bidirectional"))
    )
    (net (code "54") (name "Net-(U4-2)") (class "Default")
      (node (ref "R11") (pin "1") (pinfunction "1_1") (pintype "passive"))
      (node (ref "U4") (pin "1") (pinfunction "2_1") (pintype "bidirectional"))
    )
    (net (code "55") (name "Net-(U5-2)") (class "Default")
      (node (ref "R14") (pin "1") (pinfunction "1_1") (pintype "passive"))
      (node (ref "U5") (pin "1") (pinfunction "2_1") (pintype "bidirectional"))
    )
    (net (code "56") (name "Net-(U7-2)") (class "Default")
      (node (ref "R8") (pin "1") (pinfunction "1_1") (pintype "passive"))
      (node (ref "U7") (pin "1") (pinfunction "2_1") (pintype "bidirectional"))
    )
    (net (code "57") (name "OUT") (class "Default")
      (node (ref "IC1") (pin "3") (pinfunction "Q_3") (pintype "output"))
      (node (ref "R1") (pin "1") (pinfunction "1_1") (pintype "passive"))
      (node (ref "U1") (pin "2") (pinfunction "1A_2") (pintype "input"))
    )
    (net (code "58") (name "RESET") (class "Default")
      (node (ref "M1") (pin "RESET") (pinfunction "/RESET_RESET") (pintype "bidirectional"))
      (node (ref "M2") (pin "RESET") (pinfunction "/RESET_RESET") (pintype "bidirectional"))
      (node (ref "Q1") (pin "RESET") (pinfunction "/RESET_RESET") (pintype "bidirectional"))
    )
    (net (code "59") (name "SCL") (class "Default")
      (node (ref "M1") (pin "SCL") (pinfunction "SCL_SCL") (pintype "bidirectional"))
      (node (ref "M2") (pin "SCL") (pinfunction "SCL_SCL") (pintype "bidirectional"))
      (node (ref "Q1") (pin "SCL") (pinfunction "SCL_SCL") (pintype "bidirectional"))
    )
    (net (code "60") (name "SDA") (class "Default")
      (node (ref "M1") (pin "SDA") (pinfunction "SDA_SDA") (pintype "bidirectional"))
      (node (ref "M2") (pin "SDA") (pinfunction "SDA_SDA") (pintype "bidirectional"))
      (node (ref "Q1") (pin "SDA") (pinfunction "SDA_SDA") (pintype "bidirectional"))
    )
    (net (code "61") (name "THRS") (class "Default")
      (node (ref "IC1") (pin "6") (pinfunction "THR_6") (pintype "input"))
    )
    (net (code "62") (name "VIN") (class "Default")
      (node (ref "Q1") (pin "VIN") (pinfunction "VIN_VIN") (pintype "power_in"))
    )
    (net (code "63") (name "unconnected-(IC1-CV-Pad5)") (class "Default")
      (node (ref "IC1") (pin "5") (pinfunction "CV_5") (pintype "input"))
    )
    (net (code "64") (name "unconnected-(M1-PadIOREF)") (class "Default")
      (node (ref "M1") (pin "IOREF") (pinfunction "IOREF_IOREF") (pintype "output"))
    )
    (net (code "65") (name "unconnected-(M1-PadRESERVED)") (class "Default")
      (node (ref "M1") (pin "RESERVED") (pinfunction "RESERVED_RESERVED") (pintype "no_connect"))
    )
    (net (code "66") (name "unconnected-(M1-PadVIN)") (class "Default")
      (node (ref "M1") (pin "VIN") (pinfunction "VIN_VIN") (pintype "no_connect"))
    )
    (net (code "67") (name "unconnected-(M2-PadIOREF)") (class "Default")
      (node (ref "M2") (pin "IOREF") (pinfunction "IOREF_IOREF") (pintype "output"))
    )
    (net (code "68") (name "unconnected-(M2-PadRESERVED)") (class "Default")
      (node (ref "M2") (pin "RESERVED") (pinfunction "RESERVED_RESERVED") (pintype "no_connect"))
    )
    (net (code "69") (name "unconnected-(M2-PadVIN)") (class "Default")
      (node (ref "M2") (pin "VIN") (pinfunction "VIN_VIN") (pintype "no_connect"))
    )
    (net (code "70") (name "unconnected-(U1-2A-Pad5)") (class "Default")
      (node (ref "U1") (pin "5") (pinfunction "2A_5") (pintype "input"))
    )
    (net (code "71") (name "unconnected-(U1-2B-Pad6)") (class "Default")
      (node (ref "U1") (pin "6") (pinfunction "2B_6") (pintype "input"))
    )
    (net (code "72") (name "unconnected-(U1-2Y-Pad4)") (class "Default")
      (node (ref "U1") (pin "4") (pinfunction "2Y_4") (pintype "output"))
    )
    (net (code "73") (name "unconnected-(U1-3A-Pad8)") (class "Default")
      (node (ref "U1") (pin "8") (pinfunction "3A_8") (pintype "input"))
    )
    (net (code "74") (name "unconnected-(U1-3B-Pad9)") (class "Default")
      (node (ref "U1") (pin "9") (pinfunction "3B_9") (pintype "input"))
    )
    (net (code "75") (name "unconnected-(U1-3Y-Pad10)") (class "Default")
      (node (ref "U1") (pin "10") (pinfunction "3Y_10") (pintype "output"))
    )
    (net (code "76") (name "unconnected-(U1-4A-Pad11)") (class "Default")
      (node (ref "U1") (pin "11") (pinfunction "4A_11") (pintype "input"))
    )
    (net (code "77") (name "unconnected-(U1-4B-Pad12)") (class "Default")
      (node (ref "U1") (pin "12") (pinfunction "4B_12") (pintype "input"))
    )
    (net (code "78") (name "unconnected-(U1-4Y-Pad13)") (class "Default")
      (node (ref "U1") (pin "13") (pinfunction "4Y_13") (pintype "output"))
    )
  )
)
